# Pop-Up_5_3.net
KiCad netlist of a schematic drawn in EAGLE
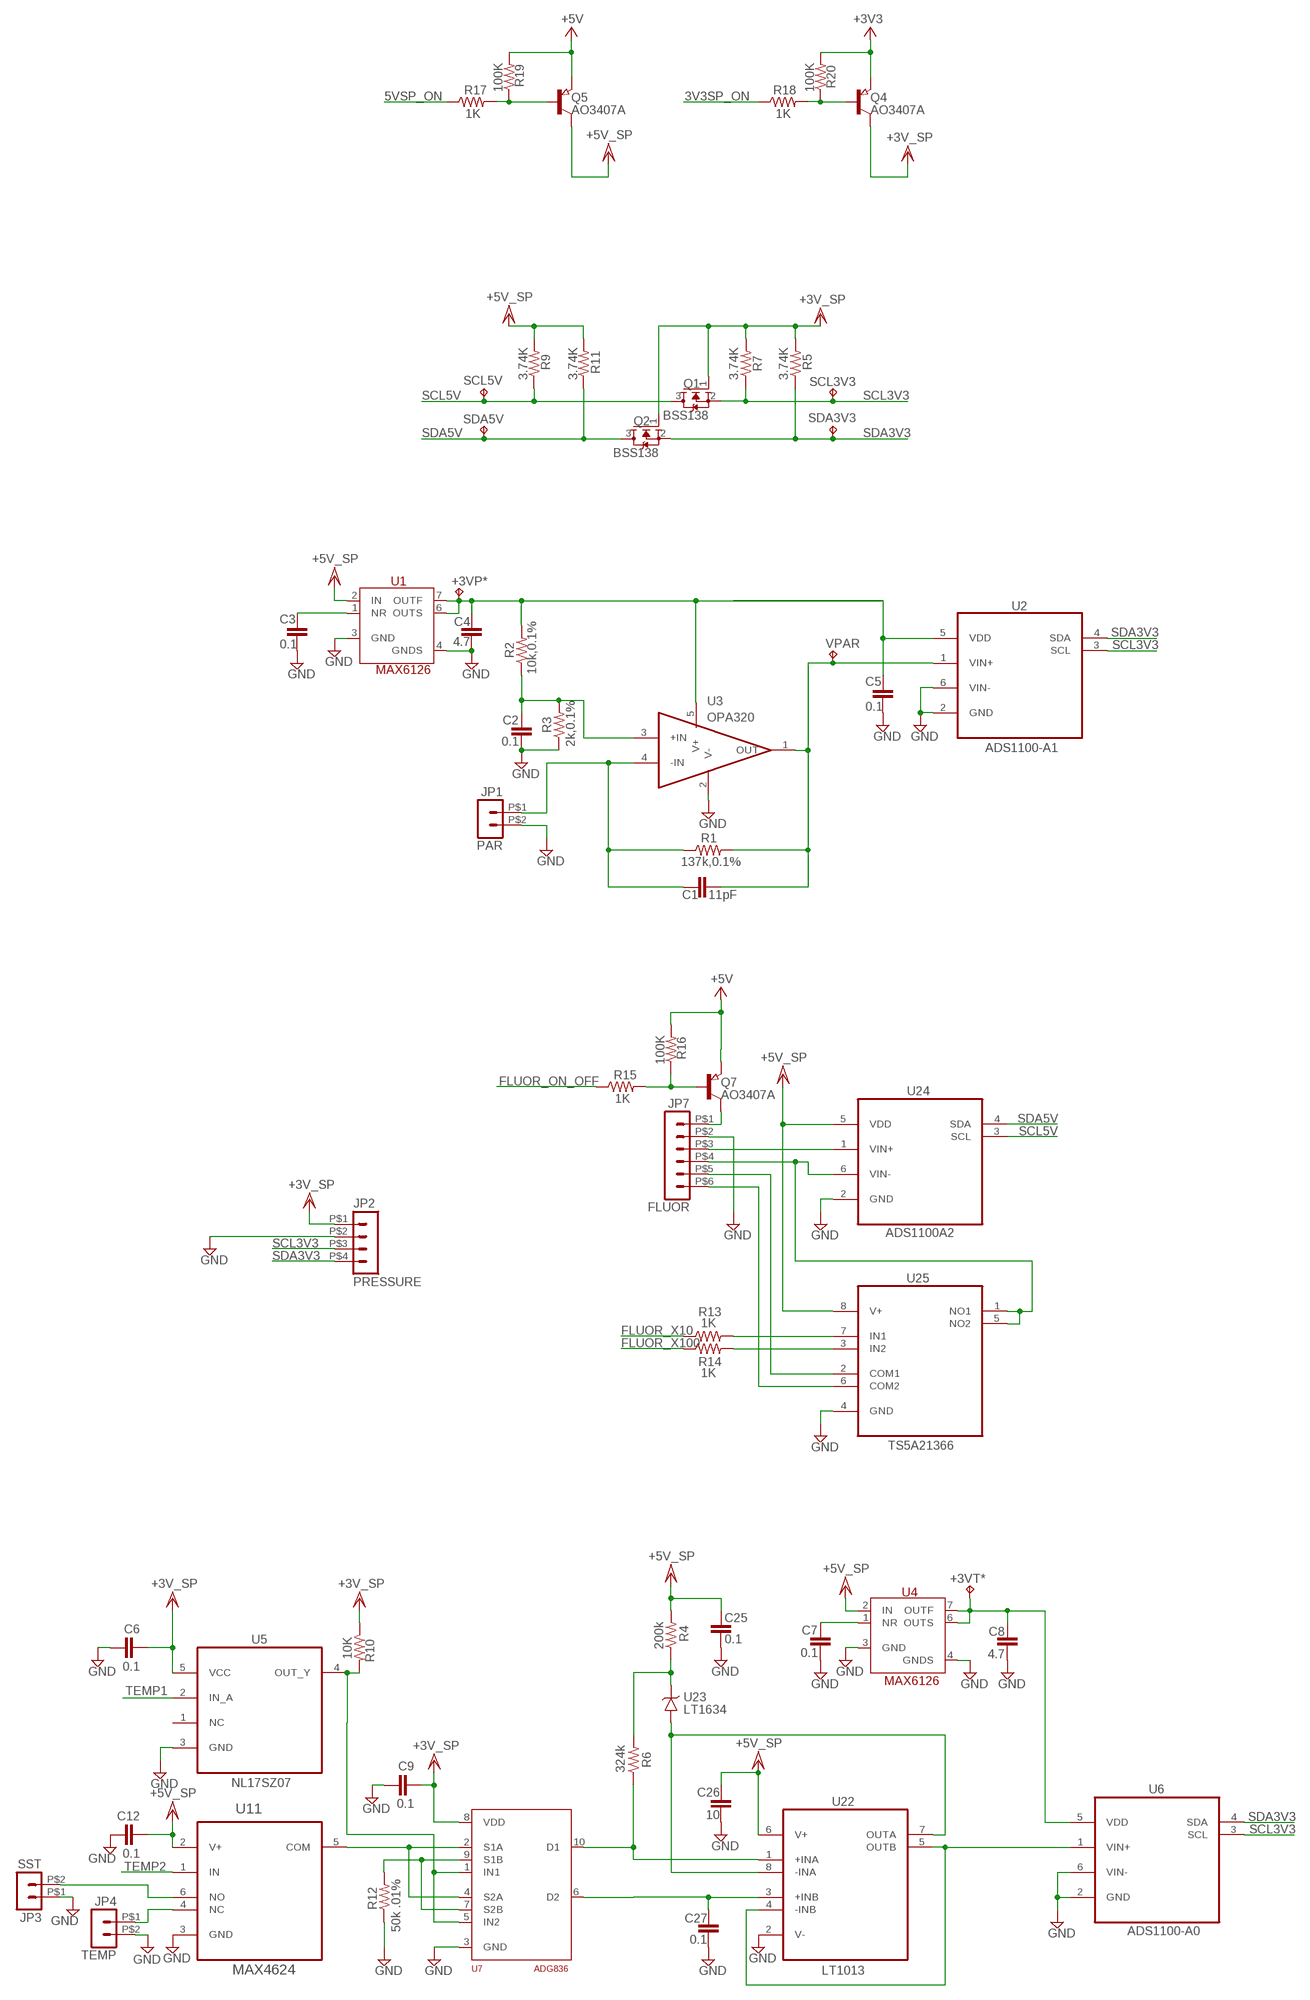
[diagram p0: schematic, sheet 1, part 1 of 2]
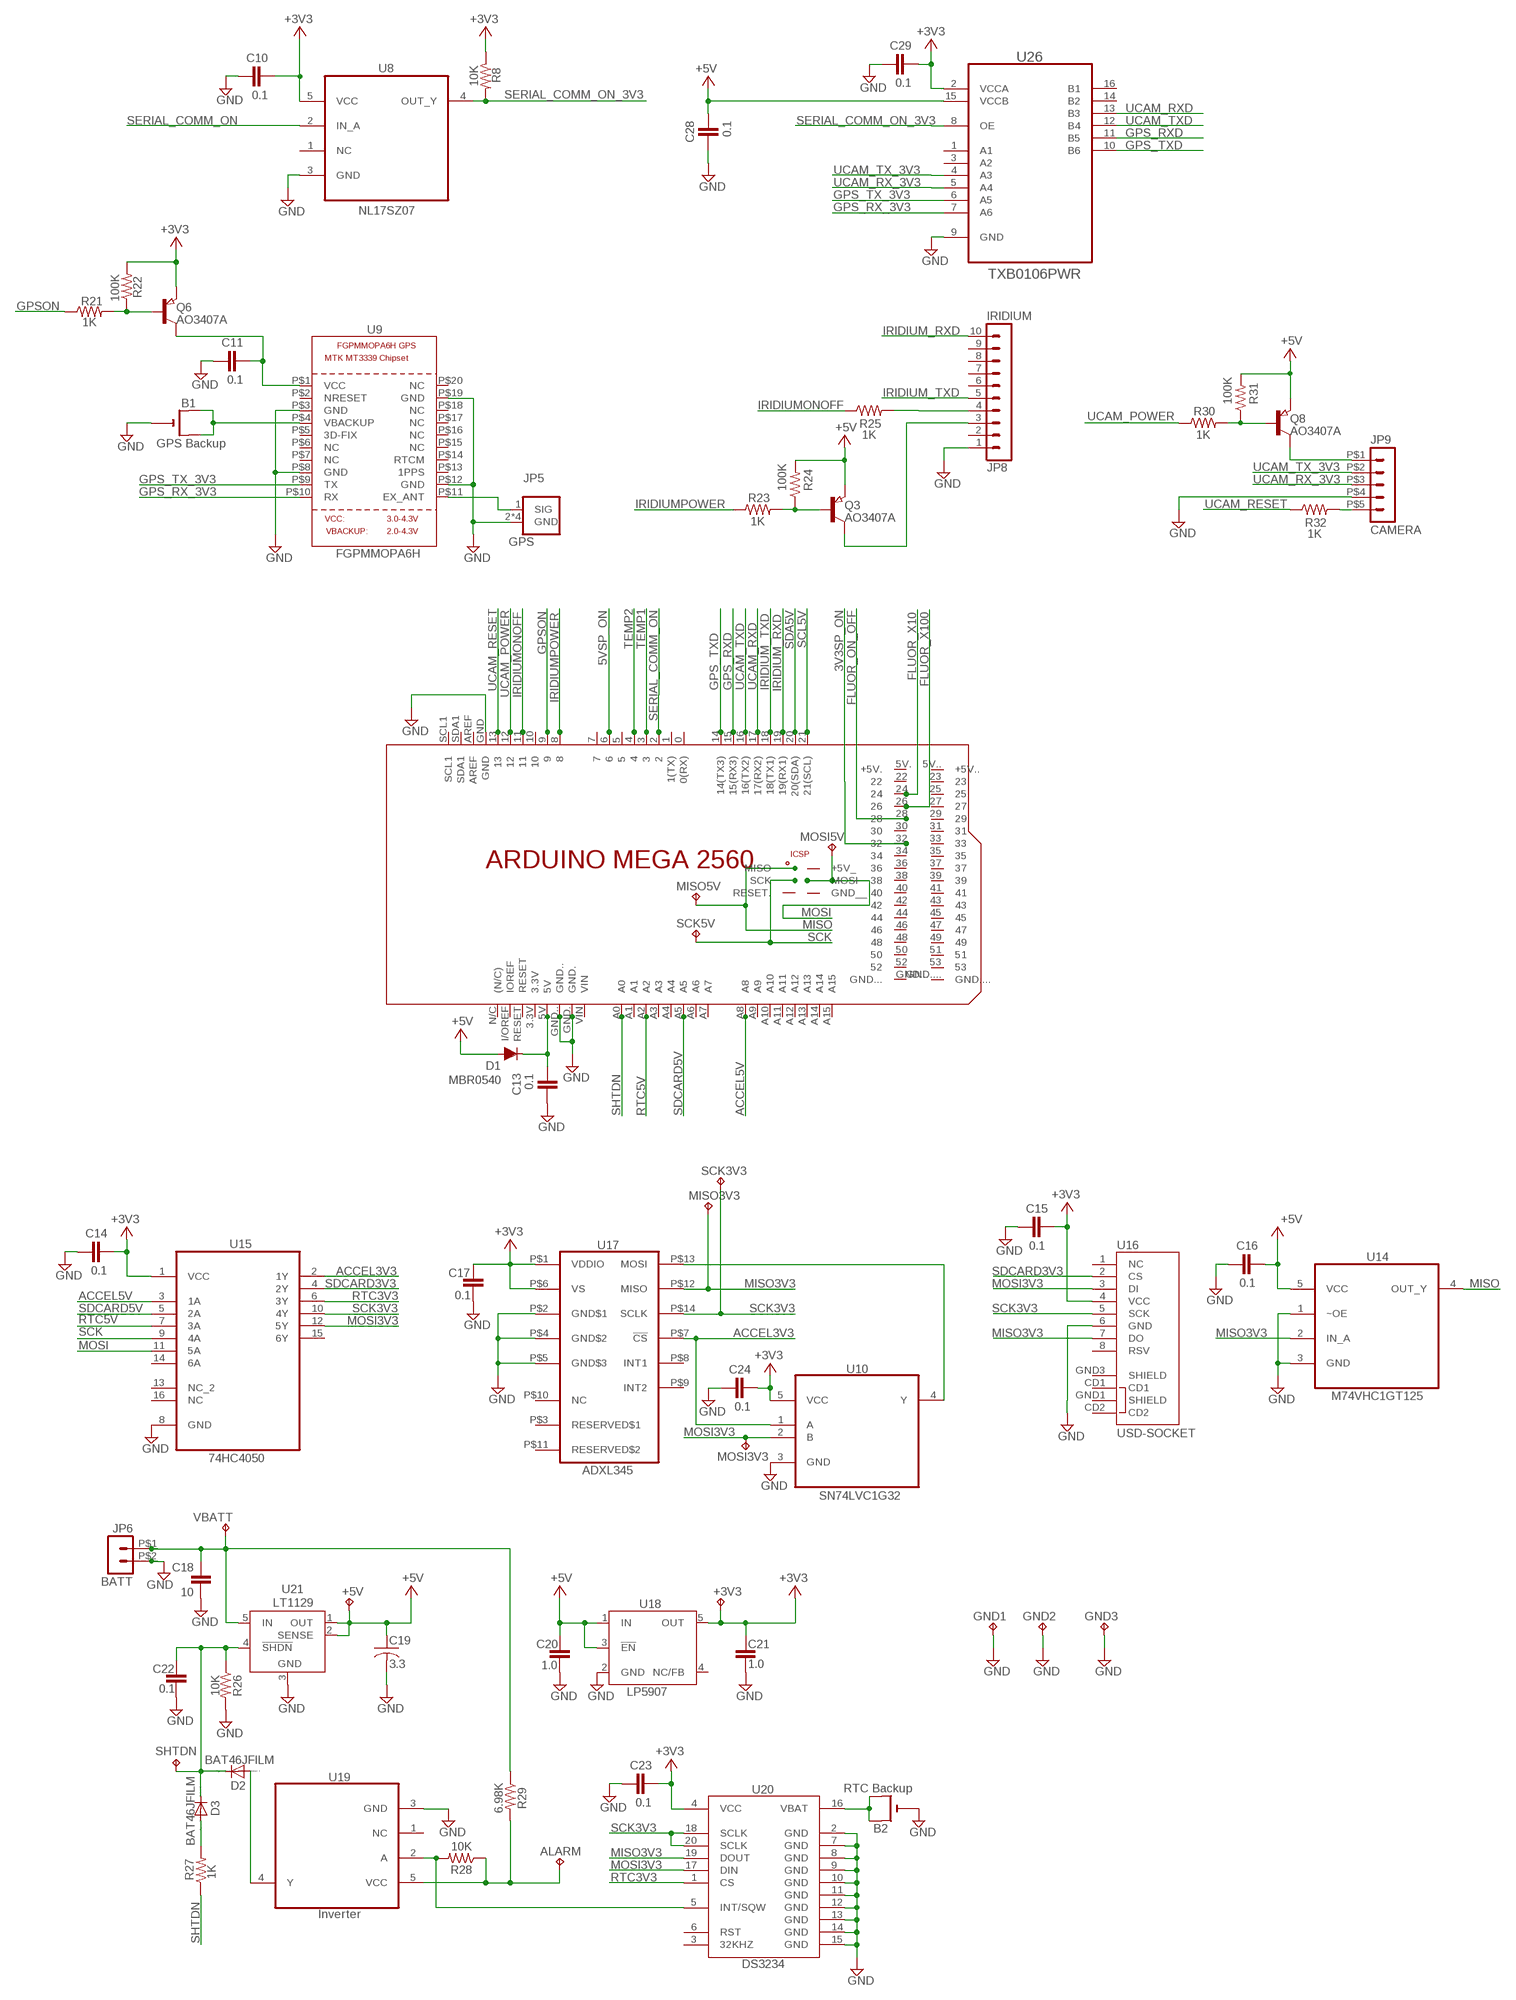
[diagram p1: schematic, sheet 1, part 2 of 2]

(export (version "E")
  (design (tool "Eeschema 10.0.6"))
  (components
    (comp (ref "+3V3")
      (value "TP-040")
      (footprint "eagle-import:TP-040")
      (libsource (lib "eagle-import") (part "TP-040"))
    )
    (comp (ref "+3VP*")
      (value "TP-040")
      (footprint "eagle-import:TP-040")
      (libsource (lib "eagle-import") (part "TP-040"))
    )
    (comp (ref "+3VT*")
      (value "TP-040")
      (footprint "eagle-import:TP-040")
      (libsource (lib "eagle-import") (part "TP-040"))
    )
    (comp (ref "+5V")
      (value "TP-040")
      (footprint "eagle-import:TP-040")
      (libsource (lib "eagle-import") (part "TP-040"))
    )
    (comp (ref "ALARM")
      (value "TP-040")
      (footprint "eagle-import:TP-040")
      (libsource (lib "eagle-import") (part "TP-040"))
    )
    (comp (ref "B1")
      (value "GPS Backup")
      (footprint "eagle-import:CR1220-SMD")
      (libsource (lib "eagle-import") (part "CR1220SMT"))
    )
    (comp (ref "B2")
      (value "RTC Backup")
      (footprint "eagle-import:CR1220-SMD")
      (libsource (lib "eagle-import") (part "CR1220SMT"))
    )
    (comp (ref "C1")
      (value "11pF")
      (footprint "eagle-import:0603-CAP")
      (fields (field (name "MPN") "2222 370 21104"))
      (libsource (lib "eagle-import") (part "CAP0603-CAP"))
    )
    (comp (ref "C2")
      (value "0.1")
      (footprint "eagle-import:0603-CAP")
      (fields (field (name "MPN") "2222 370 21104"))
      (libsource (lib "eagle-import") (part "CAP0603-CAP"))
    )
    (comp (ref "C3")
      (value "0.1")
      (footprint "eagle-import:0603-CAP")
      (fields (field (name "MPN") "2222 370 21104"))
      (libsource (lib "eagle-import") (part "CAP0603-CAP"))
    )
    (comp (ref "C4")
      (value "4.7")
      (footprint "eagle-import:0603-CAP")
      (fields (field (name "MPN") "2222 370 21104"))
      (libsource (lib "eagle-import") (part "CAP0603-CAP"))
    )
    (comp (ref "C5")
      (value "0.1")
      (footprint "eagle-import:0603-CAP")
      (fields (field (name "MPN") "2222 370 21104"))
      (libsource (lib "eagle-import") (part "CAP0603-CAP"))
    )
    (comp (ref "C6")
      (value "0.1")
      (footprint "eagle-import:0603-CAP")
      (fields (field (name "MPN") "2222 370 21104"))
      (libsource (lib "eagle-import") (part "CAP0603-CAP"))
    )
    (comp (ref "C7")
      (value "0.1")
      (footprint "eagle-import:0603-CAP")
      (fields (field (name "MPN") "2222 370 21104"))
      (libsource (lib "eagle-import") (part "CAP0603-CAP"))
    )
    (comp (ref "C8")
      (value "4.7")
      (footprint "eagle-import:0603-CAP")
      (fields (field (name "MPN") "2222 370 21104"))
      (libsource (lib "eagle-import") (part "CAP0603-CAP"))
    )
    (comp (ref "C9")
      (value "0.1")
      (footprint "eagle-import:0603-CAP")
      (fields (field (name "MPN") "2222 370 21104"))
      (libsource (lib "eagle-import") (part "CAP0603-CAP"))
    )
    (comp (ref "C10")
      (value "0.1")
      (footprint "eagle-import:0603-CAP")
      (fields (field (name "MPN") "2222 370 21104"))
      (libsource (lib "eagle-import") (part "CAP0603-CAP"))
    )
    (comp (ref "C11")
      (value "0.1")
      (footprint "eagle-import:0603-CAP")
      (fields (field (name "MPN") "2222 370 21104"))
      (libsource (lib "eagle-import") (part "CAP0603-CAP"))
    )
    (comp (ref "C12")
      (value "0.1")
      (footprint "eagle-import:0603-CAP")
      (fields (field (name "MPN") "2222 370 21104"))
      (libsource (lib "eagle-import") (part "CAP0603-CAP"))
    )
    (comp (ref "C13")
      (value "0.1")
      (footprint "eagle-import:0603-CAP")
      (fields (field (name "MPN") "2222 370 21104"))
      (libsource (lib "eagle-import") (part "CAP0603-CAP"))
    )
    (comp (ref "C14")
      (value "0.1")
      (footprint "eagle-import:0603-CAP")
      (fields (field (name "MPN") "2222 370 21104"))
      (libsource (lib "eagle-import") (part "CAP0603-CAP"))
    )
    (comp (ref "C15")
      (value "0.1")
      (footprint "eagle-import:0603-CAP")
      (fields (field (name "MPN") "2222 370 21104"))
      (libsource (lib "eagle-import") (part "CAP0603-CAP"))
    )
    (comp (ref "C16")
      (value "0.1")
      (footprint "eagle-import:0603-CAP")
      (fields (field (name "MPN") "2222 370 21104"))
      (libsource (lib "eagle-import") (part "CAP0603-CAP"))
    )
    (comp (ref "C17")
      (value "0.1")
      (footprint "eagle-import:0603-CAP")
      (fields (field (name "MPN") "2222 370 21104"))
      (libsource (lib "eagle-import") (part "CAP0603-CAP"))
    )
    (comp (ref "C18")
      (value "10")
      (footprint "eagle-import:C1206")
      (libsource (lib "eagle-import") (part "C-EUC1206"))
    )
    (comp (ref "C19")
      (value "3.3")
      (footprint "eagle-import:C1206")
      (libsource (lib "eagle-import") (part "C-USC1206"))
    )
    (comp (ref "C20")
      (value "1.0")
      (footprint "eagle-import:0603-CAP")
      (fields (field (name "MPN") "2222 370 21104"))
      (libsource (lib "eagle-import") (part "CAP0603-CAP"))
    )
    (comp (ref "C21")
      (value "1.0")
      (footprint "eagle-import:0603-CAP")
      (fields (field (name "MPN") "2222 370 21104"))
      (libsource (lib "eagle-import") (part "CAP0603-CAP"))
    )
    (comp (ref "C22")
      (value "0.1")
      (footprint "eagle-import:0603-CAP")
      (fields (field (name "MPN") "2222 370 21104"))
      (libsource (lib "eagle-import") (part "CAP0603-CAP"))
    )
    (comp (ref "C23")
      (value "0.1")
      (footprint "eagle-import:0603-CAP")
      (fields (field (name "MPN") "2222 370 21104"))
      (libsource (lib "eagle-import") (part "CAP0603-CAP"))
    )
    (comp (ref "C24")
      (value "0.1")
      (footprint "eagle-import:0603-CAP")
      (fields (field (name "MPN") "2222 370 21104"))
      (libsource (lib "eagle-import") (part "CAP0603-CAP"))
    )
    (comp (ref "C25")
      (value "0.1")
      (footprint "eagle-import:0603-CAP")
      (fields (field (name "MPN") "2222 370 21104"))
      (libsource (lib "eagle-import") (part "CAP0603-CAP"))
    )
    (comp (ref "C26")
      (value "10")
      (footprint "eagle-import:C1206")
      (fields (field (name "MPN") "2222 370 21104"))
      (libsource (lib "eagle-import") (part "C-EUC1206"))
    )
    (comp (ref "C27")
      (value "0.1")
      (footprint "eagle-import:0603-CAP")
      (fields (field (name "MPN") "2222 370 21104"))
      (libsource (lib "eagle-import") (part "CAP0603-CAP"))
    )
    (comp (ref "C28")
      (value "0.1")
      (footprint "eagle-import:0603-CAP")
      (fields (field (name "MPN") "2222 370 21104"))
      (libsource (lib "eagle-import") (part "CAP0603-CAP"))
    )
    (comp (ref "C29")
      (value "0.1")
      (footprint "eagle-import:0603-CAP")
      (fields (field (name "MPN") "2222 370 21104"))
      (libsource (lib "eagle-import") (part "CAP0603-CAP"))
    )
    (comp (ref "D1")
      (value "MBR0540")
      (footprint "eagle-import:SOD123")
      (libsource (lib "eagle-import") (part "D-FILL-SOD123"))
    )
    (comp (ref "D2")
      (value "BAT46JFILM")
      (footprint "eagle-import:SOD323-R")
      (libsource (lib "eagle-import") (part "DIODE-SOD323-R"))
    )
    (comp (ref "D3")
      (value "BAT46JFILM")
      (footprint "eagle-import:SOD323-R")
      (libsource (lib "eagle-import") (part "DIODE-SOD323-R"))
    )
    (comp (ref "GND1")
      (value "TP-040")
      (footprint "eagle-import:TP-040")
      (libsource (lib "eagle-import") (part "TP-040"))
    )
    (comp (ref "GND2")
      (value "TP-040")
      (footprint "eagle-import:TP-040")
      (libsource (lib "eagle-import") (part "TP-040"))
    )
    (comp (ref "GND3")
      (value "TP-040")
      (footprint "eagle-import:TP-040")
      (libsource (lib "eagle-import") (part "TP-040"))
    )
    (comp (ref "JP1")
      (value "PAR")
      (footprint "eagle-import:43650-0215")
      (libsource (lib "eagle-import") (part "HEADER_POS2_?43650-0215"))
    )
    (comp (ref "JP2")
      (value "PRESSURE")
      (footprint "eagle-import:43650-0415")
      (libsource (lib "eagle-import") (part "HEADER_POS4_?43650-0415"))
    )
    (comp (ref "JP3")
      (value "SST")
      (footprint "eagle-import:43650-0215")
      (libsource (lib "eagle-import") (part "HEADER_POS2_?43650-0215"))
    )
    (comp (ref "JP4")
      (value "TEMP")
      (footprint "eagle-import:43650-0215")
      (libsource (lib "eagle-import") (part "HEADER_POS2_?43650-0215"))
    )
    (comp (ref "JP5")
      (value "GPS")
      (footprint "eagle-import:AMPHENOL_901-9895-RFX")
      (fields (field (name "MPN") "901-9895-RFX"))
      (libsource (lib "eagle-import") (part "901-9895-RFX"))
    )
    (comp (ref "JP6")
      (value "BATT")
      (footprint "eagle-import:43650-0215")
      (libsource (lib "eagle-import") (part "HEADER_POS2_?43650-0215"))
    )
    (comp (ref "JP7")
      (value "FLUOR")
      (footprint "eagle-import:43045-0612")
      (libsource (lib "eagle-import") (part "HEADER_POS6_?43045-0612"))
    )
    (comp (ref "JP8")
      (value "IRIDIUM")
      (footprint "eagle-import:53398-1010")
      (libsource (lib "eagle-import") (part "53398-1010"))
    )
    (comp (ref "JP9")
      (value "CAMERA")
      (footprint "eagle-import:43650-0515")
      (libsource (lib "eagle-import") (part "HEADER_POS5_?43650-0515"))
    )
    (comp (ref "MISO3V3")
      (value "TP-040")
      (footprint "eagle-import:TP-040")
      (libsource (lib "eagle-import") (part "TP-040"))
    )
    (comp (ref "MISO5V")
      (value "TP-040")
      (footprint "eagle-import:TP-040")
      (libsource (lib "eagle-import") (part "TP-040"))
    )
    (comp (ref "MOSI3V3")
      (value "TP-040")
      (footprint "eagle-import:TP-040")
      (libsource (lib "eagle-import") (part "TP-040"))
    )
    (comp (ref "MOSI5V")
      (value "TP-040")
      (footprint "eagle-import:TP-040")
      (libsource (lib "eagle-import") (part "TP-040"))
    )
    (comp (ref "Q1")
      (value "BSS138")
      (footprint "eagle-import:SOT23")
      (libsource (lib "eagle-import") (part "MOSFET-NREFLOW"))
    )
    (comp (ref "Q2")
      (value "BSS138")
      (footprint "eagle-import:SOT23")
      (libsource (lib "eagle-import") (part "MOSFET-NREFLOW"))
    )
    (comp (ref "Q3")
      (value "AO3407A")
      (footprint "eagle-import:SOT23")
      (libsource (lib "eagle-import") (part "PNP-TRANSISTOR_SOT23"))
    )
    (comp (ref "Q4")
      (value "AO3407A")
      (footprint "eagle-import:SOT23")
      (libsource (lib "eagle-import") (part "PNP-TRANSISTOR_SOT23"))
    )
    (comp (ref "Q5")
      (value "AO3407A")
      (footprint "eagle-import:SOT23")
      (libsource (lib "eagle-import") (part "PNP-TRANSISTOR_SOT23"))
    )
    (comp (ref "Q6")
      (value "AO3407A")
      (footprint "eagle-import:SOT23")
      (libsource (lib "eagle-import") (part "PNP-TRANSISTOR_SOT23"))
    )
    (comp (ref "Q7")
      (value "AO3407A")
      (footprint "eagle-import:SOT23")
      (libsource (lib "eagle-import") (part "PNP-TRANSISTOR_SOT23"))
    )
    (comp (ref "Q8")
      (value "AO3407A")
      (footprint "eagle-import:SOT23")
      (libsource (lib "eagle-import") (part "PNP-TRANSISTOR_SOT23"))
    )
    (comp (ref "R1")
      (value "137k,0.1%")
      (footprint "eagle-import:R0603")
      (libsource (lib "eagle-import") (part "R-US_R0603"))
    )
    (comp (ref "R2")
      (value "10k,0.1%")
      (footprint "eagle-import:R0603")
      (libsource (lib "eagle-import") (part "R-US_R0603"))
    )
    (comp (ref "R3")
      (value "2k,0.1%")
      (footprint "eagle-import:R0603")
      (libsource (lib "eagle-import") (part "R-US_R0603"))
    )
    (comp (ref "R4")
      (value "200k")
      (footprint "eagle-import:R1206")
      (libsource (lib "eagle-import") (part "R-US_R1206"))
    )
    (comp (ref "R5")
      (value "3.74K")
      (footprint "eagle-import:R0603")
      (libsource (lib "eagle-import") (part "R-US_R0603"))
    )
    (comp (ref "R6")
      (value "324k")
      (footprint "eagle-import:R1206")
      (libsource (lib "eagle-import") (part "R-US_R1206"))
    )
    (comp (ref "R7")
      (value "3.74K")
      (footprint "eagle-import:R0603")
      (libsource (lib "eagle-import") (part "R-US_R0603"))
    )
    (comp (ref "R8")
      (value "10K")
      (footprint "eagle-import:R0603")
      (libsource (lib "eagle-import") (part "R-US_R0603"))
    )
    (comp (ref "R9")
      (value "3.74K")
      (footprint "eagle-import:R0603")
      (libsource (lib "eagle-import") (part "R-US_R0603"))
    )
    (comp (ref "R10")
      (value "10K")
      (footprint "eagle-import:R0603")
      (libsource (lib "eagle-import") (part "R-US_R0603"))
    )
    (comp (ref "R11")
      (value "3.74K")
      (footprint "eagle-import:R0603")
      (libsource (lib "eagle-import") (part "R-US_R0603"))
    )
    (comp (ref "R12")
      (value "50k .01%")
      (footprint "eagle-import:R2010")
      (libsource (lib "eagle-import") (part "R-US_R2010"))
    )
    (comp (ref "R13")
      (value "1K")
      (footprint "eagle-import:R0603")
      (libsource (lib "eagle-import") (part "R-US_R0603"))
    )
    (comp (ref "R14")
      (value "1K")
      (footprint "eagle-import:R0603")
      (libsource (lib "eagle-import") (part "R-US_R0603"))
    )
    (comp (ref "R15")
      (value "1K")
      (footprint "eagle-import:R0603")
      (libsource (lib "eagle-import") (part "R-US_R0603"))
    )
    (comp (ref "R16")
      (value "100K")
      (footprint "eagle-import:R0603")
      (libsource (lib "eagle-import") (part "R-US_R0603"))
    )
    (comp (ref "R17")
      (value "1K")
      (footprint "eagle-import:R0603")
      (libsource (lib "eagle-import") (part "R-US_R0603"))
    )
    (comp (ref "R18")
      (value "1K")
      (footprint "eagle-import:R0603")
      (libsource (lib "eagle-import") (part "R-US_R0603"))
    )
    (comp (ref "R19")
      (value "100K")
      (footprint "eagle-import:R0603")
      (libsource (lib "eagle-import") (part "R-US_R0603"))
    )
    (comp (ref "R20")
      (value "100K")
      (footprint "eagle-import:R0603")
      (libsource (lib "eagle-import") (part "R-US_R0603"))
    )
    (comp (ref "R21")
      (value "1K")
      (footprint "eagle-import:R0603")
      (libsource (lib "eagle-import") (part "R-US_R0603"))
    )
    (comp (ref "R22")
      (value "100K")
      (footprint "eagle-import:R0603")
      (libsource (lib "eagle-import") (part "R-US_R0603"))
    )
    (comp (ref "R23")
      (value "1K")
      (footprint "eagle-import:R0603")
      (libsource (lib "eagle-import") (part "R-US_R0603"))
    )
    (comp (ref "R24")
      (value "100K")
      (footprint "eagle-import:R0603")
      (libsource (lib "eagle-import") (part "R-US_R0603"))
    )
    (comp (ref "R25")
      (value "1K")
      (footprint "eagle-import:R0603")
      (libsource (lib "eagle-import") (part "R-US_R0603"))
    )
    (comp (ref "R26")
      (value "10K")
      (footprint "eagle-import:R0603")
      (libsource (lib "eagle-import") (part "R-US_R0603"))
    )
    (comp (ref "R27")
      (value "1K")
      (footprint "eagle-import:R0603")
      (libsource (lib "eagle-import") (part "R-US_R0603"))
    )
    (comp (ref "R28")
      (value "10K")
      (footprint "eagle-import:R0603")
      (libsource (lib "eagle-import") (part "R-US_R0603"))
    )
    (comp (ref "R29")
      (value "6.98K")
      (footprint "eagle-import:R0603")
      (libsource (lib "eagle-import") (part "R-US_R0603"))
    )
    (comp (ref "R30")
      (value "1K")
      (footprint "eagle-import:R0603")
      (libsource (lib "eagle-import") (part "R-US_R0603"))
    )
    (comp (ref "R31")
      (value "100K")
      (footprint "eagle-import:R0603")
      (libsource (lib "eagle-import") (part "R-US_R0603"))
    )
    (comp (ref "R32")
      (value "1K")
      (footprint "eagle-import:R0603")
      (libsource (lib "eagle-import") (part "R-US_R0603"))
    )
    (comp (ref "SCK3V3")
      (value "TP-040")
      (footprint "eagle-import:TP-040")
      (libsource (lib "eagle-import") (part "TP-040"))
    )
    (comp (ref "SCK5V")
      (value "TP-040")
      (footprint "eagle-import:TP-040")
      (libsource (lib "eagle-import") (part "TP-040"))
    )
    (comp (ref "SCL3V3")
      (value "TP-040")
      (footprint "eagle-import:TP-040")
      (libsource (lib "eagle-import") (part "TP-040"))
    )
    (comp (ref "SCL5V")
      (value "TP-040")
      (footprint "eagle-import:TP-040")
      (libsource (lib "eagle-import") (part "TP-040"))
    )
    (comp (ref "SDA3V3")
      (value "TP-040")
      (footprint "eagle-import:TP-040")
      (libsource (lib "eagle-import") (part "TP-040"))
    )
    (comp (ref "SDA5V")
      (value "TP-040")
      (footprint "eagle-import:TP-040")
      (libsource (lib "eagle-import") (part "TP-040"))
    )
    (comp (ref "SHTDN")
      (value "TP-040")
      (footprint "eagle-import:TP-040")
      (libsource (lib "eagle-import") (part "TP-040"))
    )
    (comp (ref "U1")
      (value "MAX6126")
      (footprint "eagle-import:SOIC127P600X175-8N")
      (libsource (lib "eagle-import") (part "MAX6126"))
    )
    (comp (ref "U2")
      (value "ADS1100-A1")
      (footprint "eagle-import:SOT95P280X145-6N")
      (fields (field (name "MPN") "ADS1100A0IDBVT"))
      (libsource (lib "eagle-import") (part "ADS1100A0IDBVT"))
    )
    (comp (ref "U3")
      (value "OPA320")
      (footprint "eagle-import:SOT95P280X145-5N")
      (fields (field (name "MPN") "OPA320AIDBVT"))
      (libsource (lib "eagle-import") (part "OPA320AIDBVT"))
    )
    (comp (ref "U4")
      (value "MAX6126")
      (footprint "eagle-import:SOIC127P600X175-8N")
      (libsource (lib "eagle-import") (part "MAX6126"))
    )
    (comp (ref "U5")
      (value "NL17SZ07")
      (footprint "eagle-import:SOT65P210X110-5N")
      (fields (field (name "MPN") "NL17SZ07DFT2G"))
      (libsource (lib "eagle-import") (part "NL17SZ07DFT2G"))
    )
    (comp (ref "U6")
      (value "ADS1100-A0")
      (footprint "eagle-import:SOT95P280X145-6N")
      (fields (field (name "MPN") "ADS1100A0IDBVT"))
      (libsource (lib "eagle-import") (part "ADS1100A0IDBVT"))
    )
    (comp (ref "U7")
      (value "ADG836")
      (footprint "eagle-import:MSOP10")
      (libsource (lib "eagle-import") (part "ADG836"))
    )
    (comp (ref "U8")
      (value "NL17SZ07")
      (footprint "eagle-import:SOT65P210X110-5N")
      (fields (field (name "MPN") "NL17SZ07DFT2G"))
      (libsource (lib "eagle-import") (part "NL17SZ07DFT2G"))
    )
    (comp (ref "U9")
      (value "FGPMMOPA6H")
      (footprint "eagle-import:FGPMMOPA6H")
      (libsource (lib "eagle-import") (part "GPS_FGPMMOPA6H"))
    )
    (comp (ref "U10")
      (value "SN74LVC1G32")
      (footprint "eagle-import:SOT65P210X110-5N")
      (fields (field (name "MPN") "SN74LVC1G32DCKT"))
      (libsource (lib "eagle-import") (part "SN74LVC1G32DCKT"))
    )
    (comp (ref "U11")
      (value "MAX4624")
      (footprint "eagle-import:SOT95P275X100-6N")
      (fields (field (name "MPN") "MAX4624EZT+T"))
      (libsource (lib "eagle-import") (part "MAX4624EZT+T"))
    )
    (comp (ref "U12")
      (value "Arduino MEGA2650")
      (footprint "eagle-import:MEGA2650_UPSIDEDOWNMOUNT")
      (libsource (lib "eagle-import") (part "MEGA2650_UPSIDEDOWNMOUNT"))
    )
    (comp (ref "U14")
      (value "M74VHC1GT125")
      (footprint "eagle-import:SOT65P210X110-5N")
      (fields (field (name "MPN") "M74VHC1GT125DF1G"))
      (libsource (lib "eagle-import") (part "M74VHC1GT125DF1G"))
    )
    (comp (ref "U15")
      (value "74HC4050")
      (footprint "eagle-import:SOIC127P600X175-16N")
      (fields (field (name "MPN") "M74HC4050RM13TR"))
      (libsource (lib "eagle-import") (part "M74HC4050RM13TR"))
    )
    (comp (ref "U16")
      (value "USD-SOCKET")
      (footprint "eagle-import:MICROSD_1_1")
      (libsource (lib "eagle-import") (part "USD-SOCKET"))
    )
    (comp (ref "U17")
      (value "ADXL345")
      (footprint "eagle-import:LGA14")
      (libsource (lib "eagle-import") (part "ADXL345"))
    )
    (comp (ref "U18")
      (value "LP5907")
      (footprint "eagle-import:SOT23-DBV")
      (fields (field (name "MF") "TEXAS INSTRUMENTS") (field (name "MPN") "TPS77033DBVT"))
      (libsource (lib "eagle-import") (part "TPS77033"))
    )
    (comp (ref "U19")
      (value "Inverter")
      (footprint "eagle-import:SOT95P280X145-5N")
      (fields (field (name "MPN") "1P1G14MDBVREPG4") (field (name "OC_NEWARK") "unknown"))
      (libsource (lib "eagle-import") (part "1P1G14MDBVREPG4"))
    )
    (comp (ref "U20")
      (value "DS3234")
      (footprint "eagle-import:DS3234")
      (libsource (lib "eagle-import") (part "DS3234"))
    )
    (comp (ref "U21")
      (value "LT1129")
      (footprint "eagle-import:Q5-DD")
      (fields (field (name "MPN") "LT1129CQ-5#PBF"))
      (libsource (lib "eagle-import") (part "LT1129CQ-5"))
    )
    (comp (ref "U22")
      (value "LT1013")
      (footprint "eagle-import:SOIC127P600X175-8N")
      (fields (field (name "MPN") "LT1013IS8#PBF"))
      (libsource (lib "eagle-import") (part "LT1013IS8PBF"))
    )
    (comp (ref "U23")
      (value "LT1634")
      (footprint "eagle-import:S8")
      (libsource (lib "eagle-import") (part "LT1634BIS8-1.25"))
    )
    (comp (ref "U24")
      (value "ADS1100A2")
      (footprint "eagle-import:SOT95P280X145-6N")
      (fields (field (name "MPN") "ADS1100A2IDBVT"))
      (libsource (lib "eagle-import") (part "ADS1100A2IDBVT"))
    )
    (comp (ref "U25")
      (value "TS5A21366")
      (footprint "eagle-import:SOP50P310X90-8N")
      (fields (field (name "MPN") "TS5A21366DCUR"))
      (libsource (lib "eagle-import") (part "TS5A21366DCUR"))
    )
    (comp (ref "U26")
      (value "TXB0106PWR")
      (footprint "eagle-import:SOP65P640X120-16N")
      (libsource (lib "eagle-import") (part "TXB0106PWR"))
    )
    (comp (ref "VBATT")
      (value "TP-040")
      (footprint "eagle-import:TP-040")
      (libsource (lib "eagle-import") (part "TP-040"))
    )
    (comp (ref "VPAR")
      (value "TP-040")
      (footprint "eagle-import:TP-040")
      (libsource (lib "eagle-import") (part "TP-040"))
    )
  )
  (nets
    (net (code "1") (name "+3V3") (class "Default")
      (node (ref "+3V3") (pin "1") (pinfunction "1_1") (pintype "passive"))
      (node (ref "C10") (pin "1") (pinfunction "1_1") (pintype "passive"))
      (node (ref "C14") (pin "1") (pinfunction "1_1") (pintype "passive"))
      (node (ref "C15") (pin "1") (pinfunction "1_1") (pintype "passive"))
      (node (ref "C17") (pin "1") (pinfunction "1_1") (pintype "passive"))
      (node (ref "C21") (pin "1") (pinfunction "1_1") (pintype "passive"))
      (node (ref "C23") (pin "1") (pinfunction "1_1") (pintype "passive"))
      (node (ref "C24") (pin "1") (pinfunction "1_1") (pintype "passive"))
      (node (ref "C29") (pin "1") (pinfunction "1_1") (pintype "passive"))
      (node (ref "Q4") (pin "2") (pinfunction "E_2") (pintype "passive"))
      (node (ref "Q6") (pin "2") (pinfunction "E_2") (pintype "passive"))
      (node (ref "R20") (pin "2") (pinfunction "2_2") (pintype "passive"))
      (node (ref "R22") (pin "2") (pinfunction "2_2") (pintype "passive"))
      (node (ref "R8") (pin "1") (pinfunction "1_1") (pintype "passive"))
      (node (ref "U10") (pin "5") (pinfunction "VCC_5") (pintype "power_in"))
      (node (ref "U15") (pin "1") (pinfunction "VCC_1") (pintype "power_in"))
      (node (ref "U16") (pin "4") (pinfunction "VCC_4") (pintype "bidirectional"))
      (node (ref "U17") (pin "P$1") (pinfunction "VDDIO_P$1") (pintype "power_in"))
      (node (ref "U17") (pin "P$6") (pinfunction "VS_P$6") (pintype "power_in"))
      (node (ref "U18") (pin "5") (pinfunction "OUT_5") (pintype "passive"))
      (node (ref "U20") (pin "4") (pinfunction "VCC_4") (pintype "bidirectional"))
      (node (ref "U26") (pin "2") (pinfunction "VCCA_2") (pintype "power_in"))
      (node (ref "U8") (pin "5") (pinfunction "VCC_5") (pintype "power_in"))
    )
    (net (code "2") (name "+3V_SP") (class "Default")
      (node (ref "C6") (pin "1") (pinfunction "1_1") (pintype "passive"))
      (node (ref "C9") (pin "1") (pinfunction "1_1") (pintype "passive"))
      (node (ref "JP2") (pin "P$1") (pinfunction "1_P$1") (pintype "passive"))
      (node (ref "Q1") (pin "1") (pinfunction "G_1") (pintype "bidirectional"))
      (node (ref "Q2") (pin "1") (pinfunction "G_1") (pintype "bidirectional"))
      (node (ref "Q4") (pin "3") (pinfunction "C_3") (pintype "passive"))
      (node (ref "R10") (pin "1") (pinfunction "1_1") (pintype "passive"))
      (node (ref "R5") (pin "2") (pinfunction "2_2") (pintype "passive"))
      (node (ref "R7") (pin "2") (pinfunction "2_2") (pintype "passive"))
      (node (ref "U5") (pin "5") (pinfunction "VCC_5") (pintype "power_in"))
      (node (ref "U7") (pin "8") (pinfunction "VDD_8") (pintype "bidirectional"))
    )
    (net (code "3") (name "+5V") (class "Default")
      (node (ref "+5V") (pin "1") (pinfunction "1_1") (pintype "passive"))
      (node (ref "C16") (pin "1") (pinfunction "1_1") (pintype "passive"))
      (node (ref "C19") (pin "1") (pinfunction "1_1") (pintype "passive"))
      (node (ref "C20") (pin "1") (pinfunction "1_1") (pintype "passive"))
      (node (ref "C28") (pin "1") (pinfunction "1_1") (pintype "passive"))
      (node (ref "D1") (pin "2") (pinfunction "A_2") (pintype "passive"))
      (node (ref "Q3") (pin "2") (pinfunction "E_2") (pintype "passive"))
      (node (ref "Q5") (pin "2") (pinfunction "E_2") (pintype "passive"))
      (node (ref "Q7") (pin "2") (pinfunction "E_2") (pintype "passive"))
      (node (ref "Q8") (pin "2") (pinfunction "E_2") (pintype "passive"))
      (node (ref "R16") (pin "2") (pinfunction "2_2") (pintype "passive"))
      (node (ref "R19") (pin "2") (pinfunction "2_2") (pintype "passive"))
      (node (ref "R24") (pin "2") (pinfunction "2_2") (pintype "passive"))
      (node (ref "R31") (pin "2") (pinfunction "2_2") (pintype "passive"))
      (node (ref "U14") (pin "5") (pinfunction "VCC_5") (pintype "power_in"))
      (node (ref "U18") (pin "1") (pinfunction "IN_1") (pintype "input"))
      (node (ref "U18") (pin "3") (pinfunction "~{EN}_3") (pintype "input"))
      (node (ref "U21") (pin "1") (pinfunction "OUT_1") (pintype "output"))
      (node (ref "U21") (pin "2") (pinfunction "SENSE_2") (pintype "input"))
      (node (ref "U26") (pin "15") (pinfunction "VCCB_15") (pintype "power_in"))
    )
    (net (code "4") (name "+5V_SP") (class "Default")
      (node (ref "C12") (pin "1") (pinfunction "1_1") (pintype "passive"))
      (node (ref "C25") (pin "1") (pinfunction "1_1") (pintype "passive"))
      (node (ref "C26") (pin "1") (pinfunction "1_1") (pintype "passive"))
      (node (ref "Q5") (pin "3") (pinfunction "C_3") (pintype "passive"))
      (node (ref "R11") (pin "2") (pinfunction "2_2") (pintype "passive"))
      (node (ref "R4") (pin "2") (pinfunction "2_2") (pintype "passive"))
      (node (ref "R9") (pin "2") (pinfunction "2_2") (pintype "passive"))
      (node (ref "U1") (pin "2") (pinfunction "IN_2") (pintype "input"))
      (node (ref "U11") (pin "2") (pinfunction "V+_2") (pintype "power_in"))
      (node (ref "U22") (pin "6") (pinfunction "V+_6") (pintype "power_in"))
      (node (ref "U24") (pin "5") (pinfunction "VDD_5") (pintype "power_in"))
      (node (ref "U25") (pin "8") (pinfunction "V+_8") (pintype "power_in"))
      (node (ref "U4") (pin "2") (pinfunction "IN_2") (pintype "input"))
    )
    (net (code "5") (name "/3V3SP_ON") (class "Default")
      (node (ref "R18") (pin "1") (pinfunction "1_1") (pintype "passive"))
      (node (ref "U12") (pin "32") (pinfunction "32_32") (pintype "bidirectional"))
    )
    (net (code "6") (name "/5VSP_ON") (class "Default")
      (node (ref "R17") (pin "1") (pinfunction "1_1") (pintype "passive"))
      (node (ref "U12") (pin "6") (pinfunction "6_6") (pintype "bidirectional"))
    )
    (net (code "7") (name "/ACCEL3V3") (class "Default")
      (node (ref "U10") (pin "1") (pinfunction "A_1") (pintype "input"))
      (node (ref "U15") (pin "2") (pinfunction "1Y_2") (pintype "output"))
      (node (ref "U17") (pin "P$7") (pinfunction "~{CS}_P$7") (pintype "input"))
    )
    (net (code "8") (name "/ACCEL5V") (class "Default")
      (node (ref "U12") (pin "A8") (pinfunction "A8_A8") (pintype "bidirectional"))
      (node (ref "U15") (pin "3") (pinfunction "1A_3") (pintype "input"))
    )
    (net (code "9") (name "/FLUOR_ON_OFF") (class "Default")
      (node (ref "R15") (pin "1") (pinfunction "1_1") (pintype "passive"))
      (node (ref "U12") (pin "28") (pinfunction "28_28") (pintype "bidirectional"))
    )
    (net (code "10") (name "/FLUOR_X10") (class "Default")
      (node (ref "R13") (pin "1") (pinfunction "1_1") (pintype "passive"))
      (node (ref "U12") (pin "24") (pinfunction "24_24") (pintype "bidirectional"))
    )
    (net (code "11") (name "/FLUOR_X100") (class "Default")
      (node (ref "R14") (pin "1") (pinfunction "1_1") (pintype "passive"))
      (node (ref "U12") (pin "26") (pinfunction "26_26") (pintype "bidirectional"))
    )
    (net (code "12") (name "/GPSON") (class "Default")
      (node (ref "R21") (pin "1") (pinfunction "1_1") (pintype "passive"))
      (node (ref "U12") (pin "9") (pinfunction "9_9") (pintype "bidirectional"))
    )
    (net (code "13") (name "/GPS_RXD") (class "Default")
      (node (ref "U12") (pin "15") (pinfunction "15(RX3)_15") (pintype "bidirectional"))
      (node (ref "U26") (pin "11") (pinfunction "B5_11") (pintype "bidirectional"))
    )
    (net (code "14") (name "/GPS_RX_3V3") (class "Default")
      (node (ref "U26") (pin "7") (pinfunction "A6_7") (pintype "bidirectional"))
      (node (ref "U9") (pin "P$10") (pinfunction "RX_P$10") (pintype "bidirectional"))
    )
    (net (code "15") (name "/GPS_TXD") (class "Default")
      (node (ref "U12") (pin "14") (pinfunction "14(TX3)_14") (pintype "bidirectional"))
      (node (ref "U26") (pin "10") (pinfunction "B6_10") (pintype "bidirectional"))
    )
    (net (code "16") (name "/GPS_TX_3V3") (class "Default")
      (node (ref "U26") (pin "6") (pinfunction "A5_6") (pintype "bidirectional"))
      (node (ref "U9") (pin "P$9") (pinfunction "TX_P$9") (pintype "bidirectional"))
    )
    (net (code "17") (name "/IRIDIUMONOFF") (class "Default")
      (node (ref "R25") (pin "1") (pinfunction "1_1") (pintype "passive"))
      (node (ref "U12") (pin "11") (pinfunction "11_11") (pintype "bidirectional"))
    )
    (net (code "18") (name "/IRIDIUMPOWER") (class "Default")
      (node (ref "R23") (pin "1") (pinfunction "1_1") (pintype "passive"))
      (node (ref "U12") (pin "8") (pinfunction "8_8") (pintype "bidirectional"))
    )
    (net (code "19") (name "/IRIDIUM_RXD") (class "Default")
      (node (ref "JP8") (pin "10") (pinfunction "10_10") (pintype "passive"))
      (node (ref "U12") (pin "19") (pinfunction "19(RX1)_19") (pintype "bidirectional"))
    )
    (net (code "20") (name "/IRIDIUM_TXD") (class "Default")
      (node (ref "JP8") (pin "5") (pinfunction "5_5") (pintype "passive"))
      (node (ref "U12") (pin "18") (pinfunction "18(TX1)_18") (pintype "bidirectional"))
    )
    (net (code "21") (name "/MISO") (class "Default")
      (node (ref "MISO5V") (pin "1") (pinfunction "1_1") (pintype "passive"))
      (node (ref "U12") (pin "MISO") (pinfunction "MISO_MISO") (pintype "bidirectional"))
      (node (ref "U14") (pin "4") (pinfunction "OUT_Y_4") (pintype "output"))
    )
    (net (code "22") (name "/MISO3V3") (class "Default")
      (node (ref "MISO3V3") (pin "1") (pinfunction "1_1") (pintype "passive"))
      (node (ref "U14") (pin "2") (pinfunction "IN_A_2") (pintype "input"))
      (node (ref "U16") (pin "7") (pinfunction "DO_7") (pintype "bidirectional"))
      (node (ref "U17") (pin "P$12") (pinfunction "MISO_P$12") (pintype "output"))
      (node (ref "U20") (pin "19") (pinfunction "DOUT_19") (pintype "bidirectional"))
    )
    (net (code "23") (name "/MOSI") (class "Default")
      (node (ref "MOSI5V") (pin "1") (pinfunction "1_1") (pintype "passive"))
      (node (ref "U12") (pin "MOSI") (pinfunction "MOSI_MOSI") (pintype "bidirectional"))
      (node (ref "U15") (pin "11") (pinfunction "5A_11") (pintype "input"))
    )
    (net (code "24") (name "/MOSI3V3") (class "Default")
      (node (ref "MOSI3V3") (pin "1") (pinfunction "1_1") (pintype "passive"))
      (node (ref "U10") (pin "2") (pinfunction "B_2") (pintype "input"))
      (node (ref "U15") (pin "12") (pinfunction "5Y_12") (pintype "output"))
      (node (ref "U16") (pin "3") (pinfunction "DI_3") (pintype "bidirectional"))
      (node (ref "U20") (pin "17") (pinfunction "DIN_17") (pintype "bidirectional"))
    )
    (net (code "25") (name "/RTC3V3") (class "Default")
      (node (ref "U15") (pin "6") (pinfunction "3Y_6") (pintype "output"))
      (node (ref "U20") (pin "1") (pinfunction "CS_1") (pintype "bidirectional"))
    )
    (net (code "26") (name "/RTC5V") (class "Default")
      (node (ref "U12") (pin "A2") (pinfunction "A2_A2") (pintype "bidirectional"))
      (node (ref "U15") (pin "7") (pinfunction "3A_7") (pintype "input"))
    )
    (net (code "27") (name "/SCK") (class "Default")
      (node (ref "SCK5V") (pin "1") (pinfunction "1_1") (pintype "passive"))
      (node (ref "U12") (pin "SCK") (pinfunction "SCK_SCK") (pintype "bidirectional"))
      (node (ref "U15") (pin "9") (pinfunction "4A_9") (pintype "input"))
    )
    (net (code "28") (name "/SCK3V3") (class "Default")
      (node (ref "SCK3V3") (pin "1") (pinfunction "1_1") (pintype "passive"))
      (node (ref "U15") (pin "10") (pinfunction "4Y_10") (pintype "output"))
      (node (ref "U16") (pin "5") (pinfunction "SCK_5") (pintype "bidirectional"))
      (node (ref "U17") (pin "P$14") (pinfunction "SCLK_P$14") (pintype "input"))
      (node (ref "U20") (pin "18") (pinfunction "SCLK_18") (pintype "bidirectional"))
      (node (ref "U20") (pin "20") (pinfunction "SCLK_20") (pintype "bidirectional"))
    )
    (net (code "29") (name "/SCL3V3") (class "Default")
      (node (ref "JP2") (pin "P$3") (pinfunction "3_P$3") (pintype "passive"))
      (node (ref "Q1") (pin "2") (pinfunction "S_2") (pintype "bidirectional"))
      (node (ref "R7") (pin "1") (pinfunction "1_1") (pintype "passive"))
      (node (ref "SCL3V3") (pin "1") (pinfunction "1_1") (pintype "passive"))
      (node (ref "U2") (pin "3") (pinfunction "SCL_3") (pintype "output"))
      (node (ref "U6") (pin "3") (pinfunction "SCL_3") (pintype "output"))
    )
    (net (code "30") (name "/SCL5V") (class "Default")
      (node (ref "Q1") (pin "3") (pinfunction "D_3") (pintype "bidirectional"))
      (node (ref "R9") (pin "1") (pinfunction "1_1") (pintype "passive"))
      (node (ref "SCL5V") (pin "1") (pinfunction "1_1") (pintype "passive"))
      (node (ref "U12") (pin "21") (pinfunction "21(SCL)_21") (pintype "bidirectional"))
      (node (ref "U24") (pin "3") (pinfunction "SCL_3") (pintype "output"))
    )
    (net (code "31") (name "/SDA3V3") (class "Default")
      (node (ref "JP2") (pin "P$4") (pinfunction "4_P$4") (pintype "passive"))
      (node (ref "Q2") (pin "2") (pinfunction "S_2") (pintype "bidirectional"))
      (node (ref "R5") (pin "1") (pinfunction "1_1") (pintype "passive"))
      (node (ref "SDA3V3") (pin "1") (pinfunction "1_1") (pintype "passive"))
      (node (ref "U2") (pin "4") (pinfunction "SDA_4") (pintype "output"))
      (node (ref "U6") (pin "4") (pinfunction "SDA_4") (pintype "output"))
    )
    (net (code "32") (name "/SDA5V") (class "Default")
      (node (ref "Q2") (pin "3") (pinfunction "D_3") (pintype "bidirectional"))
      (node (ref "R11") (pin "1") (pinfunction "1_1") (pintype "passive"))
      (node (ref "SDA5V") (pin "1") (pinfunction "1_1") (pintype "passive"))
      (node (ref "U12") (pin "20") (pinfunction "20(SDA)_20") (pintype "bidirectional"))
      (node (ref "U24") (pin "4") (pinfunction "SDA_4") (pintype "output"))
    )
    (net (code "33") (name "/SDCARD3V3") (class "Default")
      (node (ref "U15") (pin "4") (pinfunction "2Y_4") (pintype "output"))
      (node (ref "U16") (pin "2") (pinfunction "CS_2") (pintype "bidirectional"))
    )
    (net (code "34") (name "/SDCARD5V") (class "Default")
      (node (ref "U12") (pin "A5") (pinfunction "A5_A5") (pintype "bidirectional"))
      (node (ref "U15") (pin "5") (pinfunction "2A_5") (pintype "input"))
    )
    (net (code "35") (name "/SERIAL_COMM_ON") (class "Default")
      (node (ref "U12") (pin "2") (pinfunction "2_2") (pintype "bidirectional"))
      (node (ref "U8") (pin "2") (pinfunction "IN_A_2") (pintype "input"))
    )
    (net (code "36") (name "/SERIAL_COMM_ON_3V3") (class "Default")
      (node (ref "R8") (pin "2") (pinfunction "2_2") (pintype "passive"))
      (node (ref "U26") (pin "8") (pinfunction "OE_8") (pintype "input"))
      (node (ref "U8") (pin "4") (pinfunction "OUT_Y_4") (pintype "output"))
    )
    (net (code "37") (name "/SHTDN") (class "Default")
      (node (ref "R27") (pin "1") (pinfunction "1_1") (pintype "passive"))
      (node (ref "U12") (pin "A0") (pinfunction "A0_A0") (pintype "bidirectional"))
    )
    (net (code "38") (name "/TEMP1") (class "Default")
      (node (ref "U12") (pin "3") (pinfunction "3_3") (pintype "bidirectional"))
      (node (ref "U5") (pin "2") (pinfunction "IN_A_2") (pintype "input"))
    )
    (net (code "39") (name "/TEMP2") (class "Default")
      (node (ref "U11") (pin "1") (pinfunction "IN_1") (pintype "input"))
      (node (ref "U12") (pin "4") (pinfunction "4_4") (pintype "bidirectional"))
    )
    (net (code "40") (name "/UCAM_POWER") (class "Default")
      (node (ref "R30") (pin "1") (pinfunction "1_1") (pintype "passive"))
      (node (ref "U12") (pin "12") (pinfunction "12_12") (pintype "bidirectional"))
    )
    (net (code "41") (name "/UCAM_RESET") (class "Default")
      (node (ref "R32") (pin "1") (pinfunction "1_1") (pintype "passive"))
      (node (ref "U12") (pin "13") (pinfunction "13_13") (pintype "bidirectional"))
    )
    (net (code "42") (name "/UCAM_RXD") (class "Default")
      (node (ref "U12") (pin "17") (pinfunction "17(RX2)_17") (pintype "bidirectional"))
      (node (ref "U26") (pin "13") (pinfunction "B3_13") (pintype "bidirectional"))
    )
    (net (code "43") (name "/UCAM_RX_3V3") (class "Default")
      (node (ref "JP9") (pin "P$3") (pinfunction "3_P$3") (pintype "passive"))
      (node (ref "U26") (pin "5") (pinfunction "A4_5") (pintype "bidirectional"))
    )
    (net (code "44") (name "/UCAM_TXD") (class "Default")
      (node (ref "U12") (pin "16") (pinfunction "16(TX2)_16") (pintype "bidirectional"))
      (node (ref "U26") (pin "12") (pinfunction "B4_12") (pintype "bidirectional"))
    )
    (net (code "45") (name "/UCAM_TX_3V3") (class "Default")
      (node (ref "JP9") (pin "P$2") (pinfunction "2_P$2") (pintype "passive"))
      (node (ref "U26") (pin "4") (pinfunction "A3_4") (pintype "bidirectional"))
    )
    (net (code "46") (name "GND") (class "Default")
      (node (ref "B1") (pin "-") (pinfunction "-_-") (pintype "passive"))
      (node (ref "B2") (pin "-") (pinfunction "-_-") (pintype "passive"))
      (node (ref "C10") (pin "2") (pinfunction "2_2") (pintype "passive"))
      (node (ref "C11") (pin "2") (pinfunction "2_2") (pintype "passive"))
      (node (ref "C12") (pin "2") (pinfunction "2_2") (pintype "passive"))
      (node (ref "C13") (pin "2") (pinfunction "2_2") (pintype "passive"))
      (node (ref "C14") (pin "2") (pinfunction "2_2") (pintype "passive"))
      (node (ref "C15") (pin "2") (pinfunction "2_2") (pintype "passive"))
      (node (ref "C16") (pin "2") (pinfunction "2_2") (pintype "passive"))
      (node (ref "C17") (pin "2") (pinfunction "2_2") (pintype "passive"))
      (node (ref "C18") (pin "2") (pinfunction "2_2") (pintype "passive"))
      (node (ref "C19") (pin "2") (pinfunction "2_2") (pintype "passive"))
      (node (ref "C2") (pin "2") (pinfunction "2_2") (pintype "passive"))
      (node (ref "C20") (pin "2") (pinfunction "2_2") (pintype "passive"))
      (node (ref "C21") (pin "2") (pinfunction "2_2") (pintype "passive"))
      (node (ref "C22") (pin "2") (pinfunction "2_2") (pintype "passive"))
      (node (ref "C23") (pin "2") (pinfunction "2_2") (pintype "passive"))
      (node (ref "C24") (pin "2") (pinfunction "2_2") (pintype "passive"))
      (node (ref "C25") (pin "2") (pinfunction "2_2") (pintype "passive"))
      (node (ref "C26") (pin "2") (pinfunction "2_2") (pintype "passive"))
      (node (ref "C27") (pin "2") (pinfunction "2_2") (pintype "passive"))
      (node (ref "C28") (pin "2") (pinfunction "2_2") (pintype "passive"))
      (node (ref "C29") (pin "2") (pinfunction "2_2") (pintype "passive"))
      (node (ref "C3") (pin "2") (pinfunction "2_2") (pintype "passive"))
      (node (ref "C4") (pin "2") (pinfunction "2_2") (pintype "passive"))
      (node (ref "C5") (pin "1") (pinfunction "1_1") (pintype "passive"))
      (node (ref "C6") (pin "2") (pinfunction "2_2") (pintype "passive"))
      (node (ref "C7") (pin "2") (pinfunction "2_2") (pintype "passive"))
      (node (ref "C8") (pin "2") (pinfunction "2_2") (pintype "passive"))
      (node (ref "C9") (pin "2") (pinfunction "2_2") (pintype "passive"))
      (node (ref "GND1") (pin "1") (pinfunction "1_1") (pintype "passive"))
      (node (ref "GND2") (pin "1") (pinfunction "1_1") (pintype "passive"))
      (node (ref "GND3") (pin "1") (pinfunction "1_1") (pintype "passive"))
      (node (ref "JP1") (pin "P$2") (pinfunction "2_P$2") (pintype "passive"))
      (node (ref "JP2") (pin "P$2") (pinfunction "2_P$2") (pintype "passive"))
      (node (ref "JP3") (pin "P$1") (pinfunction "1_P$1") (pintype "passive"))
      (node (ref "JP4") (pin "P$2") (pinfunction "2_P$2") (pintype "passive"))
      (node (ref "JP5") (pin "2") (pinfunction "GND_2") (pintype "passive"))
      (node (ref "JP5") (pin "3") (pinfunction "GND_3") (pintype "passive"))
      (node (ref "JP5") (pin "4") (pinfunction "GND_4") (pintype "passive"))
      (node (ref "JP5") (pin "5") (pinfunction "GND_5") (pintype "passive"))
      (node (ref "JP6") (pin "P$2") (pinfunction "2_P$2") (pintype "passive"))
      (node (ref "JP7") (pin "P$2") (pinfunction "2_P$2") (pintype "passive"))
      (node (ref "JP8") (pin "1") (pinfunction "1_1") (pintype "passive"))
      (node (ref "JP9") (pin "P$4") (pinfunction "4_P$4") (pintype "passive"))
      (node (ref "R12") (pin "1") (pinfunction "1_1") (pintype "passive"))
      (node (ref "R26") (pin "2") (pinfunction "2_2") (pintype "passive"))
      (node (ref "R3") (pin "1") (pinfunction "1_1") (pintype "passive"))
      (node (ref "U1") (pin "3") (pinfunction "GND_3") (pintype "input"))
      (node (ref "U1") (pin "4") (pinfunction "GNDS_4") (pintype "input"))
      (node (ref "U10") (pin "3") (pinfunction "GND_3") (pintype "passive"))
      (node (ref "U11") (pin "3") (pinfunction "GND_3") (pintype "passive"))
      (node (ref "U12") (pin "GND") (pinfunction "GND_GND") (pintype "bidirectional"))
      (node (ref "U12") (pin "GND.") (pinfunction "GND._GND.") (pintype "bidirectional"))
      (node (ref "U12") (pin "GND..") (pinfunction "GND.._GND..") (pintype "bidirectional"))
      (node (ref "U14") (pin "1") (pinfunction "~{OE}_1") (pintype "input"))
      (node (ref "U14") (pin "3") (pinfunction "GND_3") (pintype "passive"))
      (node (ref "U15") (pin "8") (pinfunction "GND_8") (pintype "passive"))
      (node (ref "U16") (pin "6") (pinfunction "GND_6") (pintype "bidirectional"))
      (node (ref "U17") (pin "P$2") (pinfunction "GND$1_P$2") (pintype "power_in"))
      (node (ref "U17") (pin "P$4") (pinfunction "GND$2_P$4") (pintype "power_in"))
      (node (ref "U17") (pin "P$5") (pinfunction "GND$3_P$5") (pintype "power_in"))
      (node (ref "U18") (pin "2") (pinfunction "GND_2") (pintype "power_in"))
      (node (ref "U19") (pin "3") (pinfunction "GND_3") (pintype "passive"))
      (node (ref "U2") (pin "2") (pinfunction "GND_2") (pintype "passive"))
      (node (ref "U2") (pin "6") (pinfunction "VIN-_6") (pintype "input"))
      (node (ref "U20") (pin "10") (pinfunction "GND_10") (pintype "bidirectional"))
      (node (ref "U20") (pin "11") (pinfunction "GND_11") (pintype "bidirectional"))
      (node (ref "U20") (pin "12") (pinfunction "GND_12") (pintype "bidirectional"))
      (node (ref "U20") (pin "13") (pinfunction "GND_13") (pintype "bidirectional"))
      (node (ref "U20") (pin "14") (pinfunction "GND_14") (pintype "bidirectional"))
      (node (ref "U20") (pin "15") (pinfunction "GND_15") (pintype "bidirectional"))
      (node (ref "U20") (pin "2") (pinfunction "GND_2") (pintype "bidirectional"))
      (node (ref "U20") (pin "7") (pinfunction "GND_7") (pintype "bidirectional"))
      (node (ref "U20") (pin "8") (pinfunction "GND_8") (pintype "bidirectional"))
      (node (ref "U20") (pin "9") (pinfunction "GND_9") (pintype "bidirectional"))
      (node (ref "U21") (pin "3") (pinfunction "GND_3") (pintype "power_in"))
      (node (ref "U22") (pin "2") (pinfunction "V-_2") (pintype "power_in"))
      (node (ref "U24") (pin "2") (pinfunction "GND_2") (pintype "passive"))
      (node (ref "U25") (pin "4") (pinfunction "GND_4") (pintype "passive"))
      (node (ref "U26") (pin "9") (pinfunction "GND_9") (pintype "passive"))
      (node (ref "U3") (pin "2") (pinfunction "V-_2") (pintype "passive"))
      (node (ref "U4") (pin "3") (pinfunction "GND_3") (pintype "input"))
      (node (ref "U4") (pin "4") (pinfunction "GNDS_4") (pintype "input"))
      (node (ref "U5") (pin "3") (pinfunction "GND_3") (pintype "passive"))
      (node (ref "U6") (pin "2") (pinfunction "GND_2") (pintype "passive"))
      (node (ref "U6") (pin "6") (pinfunction "VIN-_6") (pintype "input"))
      (node (ref "U7") (pin "3") (pinfunction "GND_3") (pintype "bidirectional"))
      (node (ref "U8") (pin "3") (pinfunction "GND_3") (pintype "passive"))
      (node (ref "U9") (pin "P$12") (pinfunction "GND_P$12") (pintype "bidirectional"))
      (node (ref "U9") (pin "P$19") (pinfunction "GND_P$19") (pintype "bidirectional"))
      (node (ref "U9") (pin "P$3") (pinfunction "GND_P$3") (pintype "bidirectional"))
      (node (ref "U9") (pin "P$8") (pinfunction "GND_P$8") (pintype "bidirectional"))
    )
    (net (code "47") (name "Net-(B1-+)") (class "Default")
      (node (ref "B1") (pin "+$1") (pinfunction "+_+$1") (pintype "passive"))
      (node (ref "B1") (pin "+$2") (pinfunction "+1_+$2") (pintype "passive"))
      (node (ref "U9") (pin "P$4") (pinfunction "VBACKUP_P$4") (pintype "bidirectional"))
    )
    (net (code "48") (name "Net-(B2-+)") (class "Default")
      (node (ref "B2") (pin "+$1") (pinfunction "+_+$1") (pintype "passive"))
      (node (ref "B2") (pin "+$2") (pinfunction "+1_+$2") (pintype "passive"))
      (node (ref "U20") (pin "16") (pinfunction "VBAT_16") (pintype "bidirectional"))
    )
    (net (code "49") (name "Net-(D1-C)") (class "Default")
      (node (ref "C13") (pin "1") (pinfunction "1_1") (pintype "passive"))
      (node (ref "D1") (pin "1") (pinfunction "C_1") (pintype "passive"))
      (node (ref "U12") (pin "5V") (pinfunction "5V_5V") (pintype "bidirectional"))
    )
    (net (code "50") (name "Net-(D3-PadA)") (class "Default")
      (node (ref "D3") (pin "A") (pinfunction "A_A") (pintype "passive"))
      (node (ref "R27") (pin "2") (pinfunction "2_2") (pintype "passive"))
    )
    (net (code "51") (name "Net-(JP1-1)") (class "Default")
      (node (ref "C1") (pin "1") (pinfunction "1_1") (pintype "passive"))
      (node (ref "JP1") (pin "P$1") (pinfunction "1_P$1") (pintype "passive"))
      (node (ref "R1") (pin "1") (pinfunction "1_1") (pintype "passive"))
      (node (ref "U3") (pin "4") (pinfunction "-IN_4") (pintype "input"))
    )
    (net (code "52") (name "Net-(JP3-2)") (class "Default")
      (node (ref "JP3") (pin "P$2") (pinfunction "2_P$2") (pintype "passive"))
      (node (ref "U11") (pin "6") (pinfunction "NO_6") (pintype "passive"))
    )
    (net (code "53") (name "Net-(JP4-1)") (class "Default")
      (node (ref "JP4") (pin "P$1") (pinfunction "1_P$1") (pintype "passive"))
      (node (ref "U11") (pin "4") (pinfunction "NC_4") (pintype "passive"))
    )
    (net (code "54") (name "Net-(JP5-SIG)") (class "Default")
      (node (ref "JP5") (pin "1") (pinfunction "SIG_1") (pintype "passive"))
      (node (ref "U9") (pin "P$11") (pinfunction "EX_ANT_P$11") (pintype "bidirectional"))
    )
    (net (code "55") (name "Net-(JP6-1)") (class "Default")
      (node (ref "C18") (pin "1") (pinfunction "1_1") (pintype "passive"))
      (node (ref "JP6") (pin "P$1") (pinfunction "1_P$1") (pintype "passive"))
      (node (ref "R29") (pin "1") (pinfunction "1_1") (pintype "passive"))
      (node (ref "U21") (pin "5") (pinfunction "IN_5") (pintype "input"))
      (node (ref "VBATT") (pin "1") (pinfunction "1_1") (pintype "passive"))
    )
    (net (code "56") (name "Net-(JP7-1)") (class "Default")
      (node (ref "JP7") (pin "P$1") (pinfunction "1_P$1") (pintype "passive"))
      (node (ref "Q7") (pin "3") (pinfunction "C_3") (pintype "passive"))
    )
    (net (code "57") (name "Net-(JP7-3)") (class "Default")
      (node (ref "JP7") (pin "P$3") (pinfunction "3_P$3") (pintype "passive"))
      (node (ref "U24") (pin "1") (pinfunction "VIN+_1") (pintype "input"))
    )
    (net (code "58") (name "Net-(JP7-4)") (class "Default")
      (node (ref "JP7") (pin "P$4") (pinfunction "4_P$4") (pintype "passive"))
      (node (ref "U24") (pin "6") (pinfunction "VIN-_6") (pintype "input"))
      (node (ref "U25") (pin "1") (pinfunction "NO1_1") (pintype "passive"))
      (node (ref "U25") (pin "5") (pinfunction "NO2_5") (pintype "passive"))
    )
    (net (code "59") (name "Net-(JP7-5)") (class "Default")
      (node (ref "JP7") (pin "P$5") (pinfunction "5_P$5") (pintype "passive"))
      (node (ref "U25") (pin "2") (pinfunction "COM1_2") (pintype "passive"))
    )
    (net (code "60") (name "Net-(JP7-6)") (class "Default")
      (node (ref "JP7") (pin "P$6") (pinfunction "6_P$6") (pintype "passive"))
      (node (ref "U25") (pin "6") (pinfunction "COM2_6") (pintype "passive"))
    )
    (net (code "61") (name "Net-(JP8-Pad4)") (class "Default")
      (node (ref "JP8") (pin "4") (pinfunction "4_4") (pintype "passive"))
      (node (ref "R25") (pin "2") (pinfunction "2_2") (pintype "passive"))
    )
    (net (code "62") (name "Net-(JP9-1)") (class "Default")
      (node (ref "JP9") (pin "P$1") (pinfunction "1_P$1") (pintype "passive"))
      (node (ref "Q8") (pin "3") (pinfunction "C_3") (pintype "passive"))
    )
    (net (code "63") (name "Net-(JP9-5)") (class "Default")
      (node (ref "JP9") (pin "P$5") (pinfunction "5_P$5") (pintype "passive"))
      (node (ref "R32") (pin "2") (pinfunction "2_2") (pintype "passive"))
    )
    (net (code "64") (name "Net-(Q3-B)") (class "Default")
      (node (ref "Q3") (pin "1") (pinfunction "B_1") (pintype "passive"))
      (node (ref "R23") (pin "2") (pinfunction "2_2") (pintype "passive"))
      (node (ref "R24") (pin "1") (pinfunction "1_1") (pintype "passive"))
    )
    (net (code "65") (name "Net-(Q3-C)") (class "Default")
      (node (ref "JP8") (pin "3") (pinfunction "3_3") (pintype "passive"))
      (node (ref "Q3") (pin "3") (pinfunction "C_3") (pintype "passive"))
    )
    (net (code "66") (name "Net-(Q4-B)") (class "Default")
      (node (ref "Q4") (pin "1") (pinfunction "B_1") (pintype "passive"))
      (node (ref "R18") (pin "2") (pinfunction "2_2") (pintype "passive"))
      (node (ref "R20") (pin "1") (pinfunction "1_1") (pintype "passive"))
    )
    (net (code "67") (name "Net-(Q5-B)") (class "Default")
      (node (ref "Q5") (pin "1") (pinfunction "B_1") (pintype "passive"))
      (node (ref "R17") (pin "2") (pinfunction "2_2") (pintype "passive"))
      (node (ref "R19") (pin "1") (pinfunction "1_1") (pintype "passive"))
    )
    (net (code "68") (name "Net-(Q6-B)") (class "Default")
      (node (ref "Q6") (pin "1") (pinfunction "B_1") (pintype "passive"))
      (node (ref "R21") (pin "2") (pinfunction "2_2") (pintype "passive"))
      (node (ref "R22") (pin "1") (pinfunction "1_1") (pintype "passive"))
    )
    (net (code "69") (name "Net-(Q6-C)") (class "Default")
      (node (ref "C11") (pin "1") (pinfunction "1_1") (pintype "passive"))
      (node (ref "Q6") (pin "3") (pinfunction "C_3") (pintype "passive"))
      (node (ref "U9") (pin "P$1") (pinfunction "VCC_P$1") (pintype "bidirectional"))
    )
    (net (code "70") (name "Net-(Q7-B)") (class "Default")
      (node (ref "Q7") (pin "1") (pinfunction "B_1") (pintype "passive"))
      (node (ref "R15") (pin "2") (pinfunction "2_2") (pintype "passive"))
      (node (ref "R16") (pin "1") (pinfunction "1_1") (pintype "passive"))
    )
    (net (code "71") (name "Net-(Q8-B)") (class "Default")
      (node (ref "Q8") (pin "1") (pinfunction "B_1") (pintype "passive"))
      (node (ref "R30") (pin "2") (pinfunction "2_2") (pintype "passive"))
      (node (ref "R31") (pin "1") (pinfunction "1_1") (pintype "passive"))
    )
    (net (code "72") (name "Net-(U1-NR)") (class "Default")
      (node (ref "C3") (pin "1") (pinfunction "1_1") (pintype "passive"))
      (node (ref "U1") (pin "1") (pinfunction "NR_1") (pintype "bidirectional"))
    )
    (net (code "73") (name "Net-(U1-OUTF)") (class "Default")
      (node (ref "+3VP*") (pin "1") (pinfunction "1_1") (pintype "passive"))
      (node (ref "C4") (pin "1") (pinfunction "1_1") (pintype "passive"))
      (node (ref "C5") (pin "2") (pinfunction "2_2") (pintype "passive"))
      (node (ref "R2") (pin "2") (pinfunction "2_2") (pintype "passive"))
      (node (ref "U1") (pin "6") (pinfunction "OUTS_6") (pintype "output"))
      (node (ref "U1") (pin "7") (pinfunction "OUTF_7") (pintype "output"))
      (node (ref "U2") (pin "5") (pinfunction "VDD_5") (pintype "power_in"))
      (node (ref "U3") (pin "5") (pinfunction "V+_5") (pintype "power_in"))
    )
    (net (code "74") (name "Net-(U2-VIN+)") (class "Default")
      (node (ref "C1") (pin "2") (pinfunction "2_2") (pintype "passive"))
      (node (ref "R1") (pin "2") (pinfunction "2_2") (pintype "passive"))
      (node (ref "U2") (pin "1") (pinfunction "VIN+_1") (pintype "input"))
      (node (ref "U3") (pin "1") (pinfunction "OUT_1") (pintype "output"))
      (node (ref "VPAR") (pin "1") (pinfunction "1_1") (pintype "passive"))
    )
    (net (code "75") (name "Net-(U3-+IN)") (class "Default")
      (node (ref "C2") (pin "1") (pinfunction "1_1") (pintype "passive"))
      (node (ref "R2") (pin "1") (pinfunction "1_1") (pintype "passive"))
      (node (ref "R3") (pin "2") (pinfunction "2_2") (pintype "passive"))
      (node (ref "U3") (pin "3") (pinfunction "+IN_3") (pintype "input"))
    )
    (net (code "76") (name "Net-(U4-NR)") (class "Default")
      (node (ref "C7") (pin "1") (pinfunction "1_1") (pintype "passive"))
      (node (ref "U4") (pin "1") (pinfunction "NR_1") (pintype "bidirectional"))
    )
    (net (code "77") (name "Net-(U4-OUTF)") (class "Default")
      (node (ref "+3VT*") (pin "1") (pinfunction "1_1") (pintype "passive"))
      (node (ref "C8") (pin "1") (pinfunction "1_1") (pintype "passive"))
      (node (ref "U4") (pin "6") (pinfunction "OUTS_6") (pintype "output"))
      (node (ref "U4") (pin "7") (pinfunction "OUTF_7") (pintype "output"))
      (node (ref "U6") (pin "5") (pinfunction "VDD_5") (pintype "power_in"))
    )
    (net (code "78") (name "Net-(U5-OUT_Y)") (class "Default")
      (node (ref "R10") (pin "2") (pinfunction "2_2") (pintype "passive"))
      (node (ref "U5") (pin "4") (pinfunction "OUT_Y_4") (pintype "output"))
      (node (ref "U7") (pin "1") (pinfunction "IN1_1") (pintype "bidirectional"))
      (node (ref "U7") (pin "5") (pinfunction "IN2_5") (pintype "bidirectional"))
    )
    (net (code "79") (name "Net-(U7-S1B)") (class "Default")
      (node (ref "R12") (pin "2") (pinfunction "2_2") (pintype "passive"))
      (node (ref "U7") (pin "7") (pinfunction "S2B_7") (pintype "bidirectional"))
      (node (ref "U7") (pin "9") (pinfunction "S1B_9") (pintype "bidirectional"))
    )
    (net (code "80") (name "Net-(U10-Y)") (class "Default")
      (node (ref "U10") (pin "4") (pinfunction "Y_4") (pintype "output"))
      (node (ref "U17") (pin "P$13") (pinfunction "MOSI_P$13") (pintype "input"))
    )
    (net (code "81") (name "Net-(U11-COM)") (class "Default")
      (node (ref "U11") (pin "5") (pinfunction "COM_5") (pintype "output"))
      (node (ref "U7") (pin "2") (pinfunction "S1A_2") (pintype "bidirectional"))
      (node (ref "U7") (pin "4") (pinfunction "S2A_4") (pintype "bidirectional"))
    )
    (net (code "82") (name "Net-(U19-A)") (class "Default")
      (node (ref "R28") (pin "2") (pinfunction "2_2") (pintype "passive"))
      (node (ref "U19") (pin "2") (pinfunction "A_2") (pintype "input"))
      (node (ref "U20") (pin "5") (pinfunction "INT/SQW_5") (pintype "bidirectional"))
    )
    (net (code "83") (name "Net-(U19-VCC)") (class "Default")
      (node (ref "ALARM") (pin "1") (pinfunction "1_1") (pintype "passive"))
      (node (ref "R28") (pin "1") (pinfunction "1_1") (pintype "passive"))
      (node (ref "R29") (pin "2") (pinfunction "2_2") (pintype "passive"))
      (node (ref "U19") (pin "5") (pinfunction "VCC_5") (pintype "power_in"))
    )
    (net (code "84") (name "Net-(U19-Y)") (class "Default")
      (node (ref "D2") (pin "A") (pinfunction "A_A") (pintype "passive"))
      (node (ref "U19") (pin "4") (pinfunction "Y_4") (pintype "output"))
    )
    (net (code "85") (name "Net-(U21-~{SHDN})") (class "Default")
      (node (ref "C22") (pin "1") (pinfunction "1_1") (pintype "passive"))
      (node (ref "D2") (pin "C") (pinfunction "C_C") (pintype "passive"))
      (node (ref "D3") (pin "C") (pinfunction "C_C") (pintype "passive"))
      (node (ref "R26") (pin "1") (pinfunction "1_1") (pintype "passive"))
      (node (ref "SHTDN") (pin "1") (pinfunction "1_1") (pintype "passive"))
      (node (ref "U21") (pin "4") (pinfunction "~{SHDN}_4") (pintype "input"))
    )
    (net (code "86") (name "Net-(U22-+INA)") (class "Default")
      (node (ref "R6") (pin "1") (pinfunction "1_1") (pintype "passive"))
      (node (ref "U22") (pin "1") (pinfunction "+INA_1") (pintype "input"))
      (node (ref "U7") (pin "10") (pinfunction "D1_10") (pintype "bidirectional"))
    )
    (net (code "87") (name "Net-(U22-+INB)") (class "Default")
      (node (ref "C27") (pin "1") (pinfunction "1_1") (pintype "passive"))
      (node (ref "U22") (pin "3") (pinfunction "+INB_3") (pintype "input"))
      (node (ref "U7") (pin "6") (pinfunction "D2_6") (pintype "bidirectional"))
    )
    (net (code "88") (name "Net-(U22--INA)") (class "Default")
      (node (ref "U22") (pin "7") (pinfunction "OUTA_7") (pintype "output"))
      (node (ref "U22") (pin "8") (pinfunction "-INA_8") (pintype "input"))
      (node (ref "U23") (pin "4") (pinfunction "GND_4") (pintype "passive"))
    )
    (net (code "89") (name "Net-(U22--INB)") (class "Default")
      (node (ref "U22") (pin "4") (pinfunction "-INB_4") (pintype "input"))
      (node (ref "U22") (pin "5") (pinfunction "OUTB_5") (pintype "output"))
      (node (ref "U6") (pin "1") (pinfunction "VIN+_1") (pintype "input"))
    )
    (net (code "90") (name "Net-(U23-VOUT)") (class "Default")
      (node (ref "R4") (pin "1") (pinfunction "1_1") (pintype "passive"))
      (node (ref "R6") (pin "2") (pinfunction "2_2") (pintype "passive"))
      (node (ref "U23") (pin "6") (pinfunction "VOUT_6") (pintype "passive"))
    )
    (net (code "91") (name "Net-(U25-IN1)") (class "Default")
      (node (ref "R13") (pin "2") (pinfunction "2_2") (pintype "passive"))
      (node (ref "U25") (pin "7") (pinfunction "IN1_7") (pintype "input"))
    )
    (net (code "92") (name "Net-(U25-IN2)") (class "Default")
      (node (ref "R14") (pin "2") (pinfunction "2_2") (pintype "passive"))
      (node (ref "U25") (pin "3") (pinfunction "IN2_3") (pintype "input"))
    )
    (net (code "93") (name "unconnected-(JP8-Pad2)") (class "Default")
      (node (ref "JP8") (pin "2") (pinfunction "2_2") (pintype "passive"))
    )
    (net (code "94") (name "unconnected-(JP8-Pad6)") (class "Default")
      (node (ref "JP8") (pin "6") (pinfunction "6_6") (pintype "passive"))
    )
    (net (code "95") (name "unconnected-(JP8-Pad7)") (class "Default")
      (node (ref "JP8") (pin "7") (pinfunction "7_7") (pintype "passive"))
    )
    (net (code "96") (name "unconnected-(JP8-Pad8)") (class "Default")
      (node (ref "JP8") (pin "8") (pinfunction "8_8") (pintype "passive"))
    )
    (net (code "97") (name "unconnected-(JP8-Pad9)") (class "Default")
      (node (ref "JP8") (pin "9") (pinfunction "9_9") (pintype "passive"))
    )
    (net (code "98") (name "unconnected-(U5-NC-Pad1)") (class "Default")
      (node (ref "U5") (pin "1") (pinfunction "NC_1") (pintype "no_connect"))
    )
    (net (code "99") (name "unconnected-(U8-NC-Pad1)") (class "Default")
      (node (ref "U8") (pin "1") (pinfunction "NC_1") (pintype "no_connect"))
    )
    (net (code "100") (name "unconnected-(U9-1PPS-PadP$13)") (class "Default")
      (node (ref "U9") (pin "P$13") (pinfunction "1PPS_P$13") (pintype "bidirectional"))
    )
    (net (code "101") (name "unconnected-(U9-3D-FIX-PadP$5)") (class "Default")
      (node (ref "U9") (pin "P$5") (pinfunction "3D-FIX_P$5") (pintype "bidirectional"))
    )
    (net (code "102") (name "unconnected-(U9-NC-PadP$6)") (class "Default")
      (node (ref "U9") (pin "P$6") (pinfunction "NC_P$6") (pintype "bidirectional"))
    )
    (net (code "103") (name "unconnected-(U9-NC-PadP$7)") (class "Default")
      (node (ref "U9") (pin "P$7") (pinfunction "NC_P$7") (pintype "bidirectional"))
    )
    (net (code "104") (name "unconnected-(U9-NC-PadP$15)") (class "Default")
      (node (ref "U9") (pin "P$15") (pinfunction "NC_P$15") (pintype "bidirectional"))
    )
    (net (code "105") (name "unconnected-(U9-NC-PadP$16)") (class "Default")
      (node (ref "U9") (pin "P$16") (pinfunction "NC_P$16") (pintype "bidirectional"))
    )
    (net (code "106") (name "unconnected-(U9-NC-PadP$17)") (class "Default")
      (node (ref "U9") (pin "P$17") (pinfunction "NC_P$17") (pintype "bidirectional"))
    )
    (net (code "107") (name "unconnected-(U9-NC-PadP$18)") (class "Default")
      (node (ref "U9") (pin "P$18") (pinfunction "NC_P$18") (pintype "bidirectional"))
    )
    (net (code "108") (name "unconnected-(U9-NC-PadP$20)") (class "Default")
      (node (ref "U9") (pin "P$20") (pinfunction "NC_P$20") (pintype "bidirectional"))
    )
    (net (code "109") (name "unconnected-(U9-NRESET-PadP$2)") (class "Default")
      (node (ref "U9") (pin "P$2") (pinfunction "NRESET_P$2") (pintype "bidirectional"))
    )
    (net (code "110") (name "unconnected-(U9-RTCM-PadP$14)") (class "Default")
      (node (ref "U9") (pin "P$14") (pinfunction "RTCM_P$14") (pintype "bidirectional"))
    )
    (net (code "111") (name "unconnected-(U12-(N{slash}C)-PadN{slash}C)") (class "Default")
      (node (ref "U12") (pin "N/C") (pinfunction "(N/C)_N/C") (pintype "bidirectional"))
    )
    (net (code "112") (name "unconnected-(U12-+5V.-Pad5V.)") (class "Default")
      (node (ref "U12") (pin "5V.") (pinfunction "+5V._5V.") (pintype "bidirectional"))
    )
    (net (code "113") (name "unconnected-(U12-+5V..-Pad5V..)") (class "Default")
      (node (ref "U12") (pin "5V..") (pinfunction "+5V.._5V..") (pintype "bidirectional"))
    )
    (net (code "114") (name "unconnected-(U12-0(RX)-Pad0)") (class "Default")
      (node (ref "U12") (pin "0") (pinfunction "0(RX)_0") (pintype "bidirectional"))
    )
    (net (code "115") (name "unconnected-(U12-1(TX)-Pad1)") (class "Default")
      (node (ref "U12") (pin "1") (pinfunction "1(TX)_1") (pintype "bidirectional"))
    )
    (net (code "116") (name "unconnected-(U12-IOREF-PadI{slash}OREF)") (class "Default")
      (node (ref "U12") (pin "I/OREF") (pinfunction "IOREF_I/OREF") (pintype "bidirectional"))
    )
    (net (code "117") (name "unconnected-(U12-Pad+5V_)") (class "Default")
      (node (ref "U12") (pin "+5V_") (pinfunction "+5V__+5V_") (pintype "bidirectional"))
    )
    (net (code "118") (name "unconnected-(U12-Pad3.3V)") (class "Default")
      (node (ref "U12") (pin "3.3V") (pinfunction "3.3V_3.3V") (pintype "bidirectional"))
    )
    (net (code "119") (name "unconnected-(U12-Pad5)") (class "Default")
      (node (ref "U12") (pin "5") (pinfunction "5_5") (pintype "bidirectional"))
    )
    (net (code "120") (name "unconnected-(U12-Pad7)") (class "Default")
      (node (ref "U12") (pin "7") (pinfunction "7_7") (pintype "bidirectional"))
    )
    (net (code "121") (name "unconnected-(U12-Pad10)") (class "Default")
      (node (ref "U12") (pin "10") (pinfunction "10_10") (pintype "bidirectional"))
    )
    (net (code "122") (name "unconnected-(U12-Pad22)") (class "Default")
      (node (ref "U12") (pin "22") (pinfunction "22_22") (pintype "bidirectional"))
    )
    (net (code "123") (name "unconnected-(U12-Pad23)") (class "Default")
      (node (ref "U12") (pin "23") (pinfunction "23_23") (pintype "bidirectional"))
    )
    (net (code "124") (name "unconnected-(U12-Pad25)") (class "Default")
      (node (ref "U12") (pin "25") (pinfunction "25_25") (pintype "bidirectional"))
    )
    (net (code "125") (name "unconnected-(U12-Pad27)") (class "Default")
      (node (ref "U12") (pin "27") (pinfunction "27_27") (pintype "bidirectional"))
    )
    (net (code "126") (name "unconnected-(U12-Pad29)") (class "Default")
      (node (ref "U12") (pin "29") (pinfunction "29_29") (pintype "bidirectional"))
    )
    (net (code "127") (name "unconnected-(U12-Pad30)") (class "Default")
      (node (ref "U12") (pin "30") (pinfunction "30_30") (pintype "bidirectional"))
    )
    (net (code "128") (name "unconnected-(U12-Pad31)") (class "Default")
      (node (ref "U12") (pin "31") (pinfunction "31_31") (pintype "bidirectional"))
    )
    (net (code "129") (name "unconnected-(U12-Pad33)") (class "Default")
      (node (ref "U12") (pin "33") (pinfunction "33_33") (pintype "bidirectional"))
    )
    (net (code "130") (name "unconnected-(U12-Pad34)") (class "Default")
      (node (ref "U12") (pin "34") (pinfunction "34_34") (pintype "bidirectional"))
    )
    (net (code "131") (name "unconnected-(U12-Pad35)") (class "Default")
      (node (ref "U12") (pin "35") (pinfunction "35_35") (pintype "bidirectional"))
    )
    (net (code "132") (name "unconnected-(U12-Pad36)") (class "Default")
      (node (ref "U12") (pin "36") (pinfunction "36_36") (pintype "bidirectional"))
    )
    (net (code "133") (name "unconnected-(U12-Pad37)") (class "Default")
      (node (ref "U12") (pin "37") (pinfunction "37_37") (pintype "bidirectional"))
    )
    (net (code "134") (name "unconnected-(U12-Pad38)") (class "Default")
      (node (ref "U12") (pin "38") (pinfunction "38_38") (pintype "bidirectional"))
    )
    (net (code "135") (name "unconnected-(U12-Pad39)") (class "Default")
      (node (ref "U12") (pin "39") (pinfunction "39_39") (pintype "bidirectional"))
    )
    (net (code "136") (name "unconnected-(U12-Pad40)") (class "Default")
      (node (ref "U12") (pin "40") (pinfunction "40_40") (pintype "bidirectional"))
    )
    (net (code "137") (name "unconnected-(U12-Pad41)") (class "Default")
      (node (ref "U12") (pin "41") (pinfunction "41_41") (pintype "bidirectional"))
    )
    (net (code "138") (name "unconnected-(U12-Pad42)") (class "Default")
      (node (ref "U12") (pin "42") (pinfunction "42_42") (pintype "bidirectional"))
    )
    (net (code "139") (name "unconnected-(U12-Pad43)") (class "Default")
      (node (ref "U12") (pin "43") (pinfunction "43_43") (pintype "bidirectional"))
    )
    (net (code "140") (name "unconnected-(U12-Pad44)") (class "Default")
      (node (ref "U12") (pin "44") (pinfunction "44_44") (pintype "bidirectional"))
    )
    (net (code "141") (name "unconnected-(U12-Pad45)") (class "Default")
      (node (ref "U12") (pin "45") (pinfunction "45_45") (pintype "bidirectional"))
    )
    (net (code "142") (name "unconnected-(U12-Pad46)") (class "Default")
      (node (ref "U12") (pin "46") (pinfunction "46_46") (pintype "bidirectional"))
    )
    (net (code "143") (name "unconnected-(U12-Pad47)") (class "Default")
      (node (ref "U12") (pin "47") (pinfunction "47_47") (pintype "bidirectional"))
    )
    (net (code "144") (name "unconnected-(U12-Pad48)") (class "Default")
      (node (ref "U12") (pin "48") (pinfunction "48_48") (pintype "bidirectional"))
    )
    (net (code "145") (name "unconnected-(U12-Pad49)") (class "Default")
      (node (ref "U12") (pin "49") (pinfunction "49_49") (pintype "bidirectional"))
    )
    (net (code "146") (name "unconnected-(U12-Pad50)") (class "Default")
      (node (ref "U12") (pin "50") (pinfunction "50_50") (pintype "bidirectional"))
    )
    (net (code "147") (name "unconnected-(U12-Pad51)") (class "Default")
      (node (ref "U12") (pin "51") (pinfunction "51_51") (pintype "bidirectional"))
    )
    (net (code "148") (name "unconnected-(U12-Pad52)") (class "Default")
      (node (ref "U12") (pin "52") (pinfunction "52_52") (pintype "bidirectional"))
    )
    (net (code "149") (name "unconnected-(U12-Pad53)") (class "Default")
      (node (ref "U12") (pin "53") (pinfunction "53_53") (pintype "bidirectional"))
    )
    (net (code "150") (name "unconnected-(U12-PadA1)") (class "Default")
      (node (ref "U12") (pin "A1") (pinfunction "A1_A1") (pintype "bidirectional"))
    )
    (net (code "151") (name "unconnected-(U12-PadA3)") (class "Default")
      (node (ref "U12") (pin "A3") (pinfunction "A3_A3") (pintype "bidirectional"))
    )
    (net (code "152") (name "unconnected-(U12-PadA4)") (class "Default")
      (node (ref "U12") (pin "A4") (pinfunction "A4_A4") (pintype "bidirectional"))
    )
    (net (code "153") (name "unconnected-(U12-PadA6)") (class "Default")
      (node (ref "U12") (pin "A6") (pinfunction "A6_A6") (pintype "bidirectional"))
    )
    (net (code "154") (name "unconnected-(U12-PadA7)") (class "Default")
      (node (ref "U12") (pin "A7") (pinfunction "A7_A7") (pintype "bidirectional"))
    )
    (net (code "155") (name "unconnected-(U12-PadA9)") (class "Default")
      (node (ref "U12") (pin "A9") (pinfunction "A9_A9") (pintype "bidirectional"))
    )
    (net (code "156") (name "unconnected-(U12-PadA10)") (class "Default")
      (node (ref "U12") (pin "A10") (pinfunction "A10_A10") (pintype "bidirectional"))
    )
    (net (code "157") (name "unconnected-(U12-PadA11)") (class "Default")
      (node (ref "U12") (pin "A11") (pinfunction "A11_A11") (pintype "bidirectional"))
    )
    (net (code "158") (name "unconnected-(U12-PadA12)") (class "Default")
      (node (ref "U12") (pin "A12") (pinfunction "A12_A12") (pintype "bidirectional"))
    )
    (net (code "159") (name "unconnected-(U12-PadA13)") (class "Default")
      (node (ref "U12") (pin "A13") (pinfunction "A13_A13") (pintype "bidirectional"))
    )
    (net (code "160") (name "unconnected-(U12-PadA14)") (class "Default")
      (node (ref "U12") (pin "A14") (pinfunction "A14_A14") (pintype "bidirectional"))
    )
    (net (code "161") (name "unconnected-(U12-PadA15)") (class "Default")
      (node (ref "U12") (pin "A15") (pinfunction "A15_A15") (pintype "bidirectional"))
    )
    (net (code "162") (name "unconnected-(U12-PadAREF)") (class "Default")
      (node (ref "U12") (pin "AREF") (pinfunction "AREF_AREF") (pintype "bidirectional"))
    )
    (net (code "163") (name "unconnected-(U12-PadGND...)") (class "Default")
      (node (ref "U12") (pin "GND...") (pinfunction "GND..._GND...") (pintype "bidirectional"))
    )
    (net (code "164") (name "unconnected-(U12-PadGND....)") (class "Default")
      (node (ref "U12") (pin "GND....") (pinfunction "GND...._GND....") (pintype "bidirectional"))
    )
    (net (code "165") (name "unconnected-(U12-PadGND__)") (class "Default")
      (node (ref "U12") (pin "GND__") (pinfunction "GND___GND__") (pintype "bidirectional"))
    )
    (net (code "166") (name "unconnected-(U12-PadRESET)") (class "Default")
      (node (ref "U12") (pin "RESET") (pinfunction "RESET_RESET") (pintype "bidirectional"))
    )
    (net (code "167") (name "unconnected-(U12-PadRESET.)") (class "Default")
      (node (ref "U12") (pin "RESET.") (pinfunction "RESET._RESET.") (pintype "bidirectional"))
    )
    (net (code "168") (name "unconnected-(U12-PadSCL1)") (class "Default")
      (node (ref "U12") (pin "SCL1") (pinfunction "SCL1_SCL1") (pintype "bidirectional"))
    )
    (net (code "169") (name "unconnected-(U12-PadSDA1)") (class "Default")
      (node (ref "U12") (pin "SDA1") (pinfunction "SDA1_SDA1") (pintype "bidirectional"))
    )
    (net (code "170") (name "unconnected-(U12-PadVIN)") (class "Default")
      (node (ref "U12") (pin "VIN") (pinfunction "VIN_VIN") (pintype "bidirectional"))
    )
    (net (code "171") (name "unconnected-(U15-6A-Pad14)") (class "Default")
      (node (ref "U15") (pin "14") (pinfunction "6A_14") (pintype "input"))
    )
    (net (code "172") (name "unconnected-(U15-6Y-Pad15)") (class "Default")
      (node (ref "U15") (pin "15") (pinfunction "6Y_15") (pintype "output"))
    )
    (net (code "173") (name "unconnected-(U15-NC-Pad16)") (class "Default")
      (node (ref "U15") (pin "16") (pinfunction "NC_16") (pintype "no_connect"))
    )
    (net (code "174") (name "unconnected-(U15-NC_2-Pad13)") (class "Default")
      (node (ref "U15") (pin "13") (pinfunction "NC_2_13") (pintype "no_connect"))
    )
    (net (code "175") (name "unconnected-(U16-NC-Pad1)") (class "Default")
      (node (ref "U16") (pin "1") (pinfunction "NC_1") (pintype "bidirectional"))
    )
    (net (code "176") (name "unconnected-(U16-PadCD1)") (class "Default")
      (node (ref "U16") (pin "CD1") (pinfunction "CD1_CD1") (pintype "bidirectional"))
    )
    (net (code "177") (name "unconnected-(U16-PadCD2)") (class "Default")
      (node (ref "U16") (pin "CD2") (pinfunction "CD2_CD2") (pintype "bidirectional"))
    )
    (net (code "178") (name "unconnected-(U16-RSV-Pad8)") (class "Default")
      (node (ref "U16") (pin "8") (pinfunction "RSV_8") (pintype "bidirectional"))
    )
    (net (code "179") (name "unconnected-(U16-SHIELD-PadGND1)") (class "Default")
      (node (ref "U16") (pin "GND1") (pinfunction "SHIELD_GND1") (pintype "bidirectional"))
    )
    (net (code "180") (name "unconnected-(U16-SHIELD-PadGND3)") (class "Default")
      (node (ref "U16") (pin "GND3") (pinfunction "SHIELD_GND3") (pintype "bidirectional"))
    )
    (net (code "181") (name "unconnected-(U17-INT1-PadP$8)") (class "Default")
      (node (ref "U17") (pin "P$8") (pinfunction "INT1_P$8") (pintype "output"))
    )
    (net (code "182") (name "unconnected-(U17-INT2-PadP$9)") (class "Default")
      (node (ref "U17") (pin "P$9") (pinfunction "INT2_P$9") (pintype "output"))
    )
    (net (code "183") (name "unconnected-(U17-NC-PadP$10)") (class "Default")
      (node (ref "U17") (pin "P$10") (pinfunction "NC_P$10") (pintype "bidirectional"))
    )
    (net (code "184") (name "unconnected-(U17-RESERVED$1-PadP$3)") (class "Default")
      (node (ref "U17") (pin "P$3") (pinfunction "RESERVED$1_P$3") (pintype "bidirectional"))
    )
    (net (code "185") (name "unconnected-(U17-RESERVED$2-PadP$11)") (class "Default")
      (node (ref "U17") (pin "P$11") (pinfunction "RESERVED$2_P$11") (pintype "bidirectional"))
    )
    (net (code "186") (name "unconnected-(U18-NC{slash}FB-Pad4)") (class "Default")
      (node (ref "U18") (pin "4") (pinfunction "NC/FB_4") (pintype "passive"))
    )
    (net (code "187") (name "unconnected-(U19-NC-Pad1)") (class "Default")
      (node (ref "U19") (pin "1") (pinfunction "NC_1") (pintype "no_connect"))
    )
    (net (code "188") (name "unconnected-(U20-32KHZ-Pad3)") (class "Default")
      (node (ref "U20") (pin "3") (pinfunction "32KHZ_3") (pintype "bidirectional"))
    )
    (net (code "189") (name "unconnected-(U20-RST-Pad6)") (class "Default")
      (node (ref "U20") (pin "6") (pinfunction "RST_6") (pintype "bidirectional"))
    )
    (net (code "190") (name "unconnected-(U26-A1-Pad1)") (class "Default")
      (node (ref "U26") (pin "1") (pinfunction "A1_1") (pintype "bidirectional"))
    )
    (net (code "191") (name "unconnected-(U26-A2-Pad3)") (class "Default")
      (node (ref "U26") (pin "3") (pinfunction "A2_3") (pintype "bidirectional"))
    )
    (net (code "192") (name "unconnected-(U26-B1-Pad16)") (class "Default")
      (node (ref "U26") (pin "16") (pinfunction "B1_16") (pintype "bidirectional"))
    )
    (net (code "193") (name "unconnected-(U26-B2-Pad14)") (class "Default")
      (node (ref "U26") (pin "14") (pinfunction "B2_14") (pintype "bidirectional"))
    )
  )
)
